# MCU.net
KiCad netlist of a schematic drawn in Altium Designer
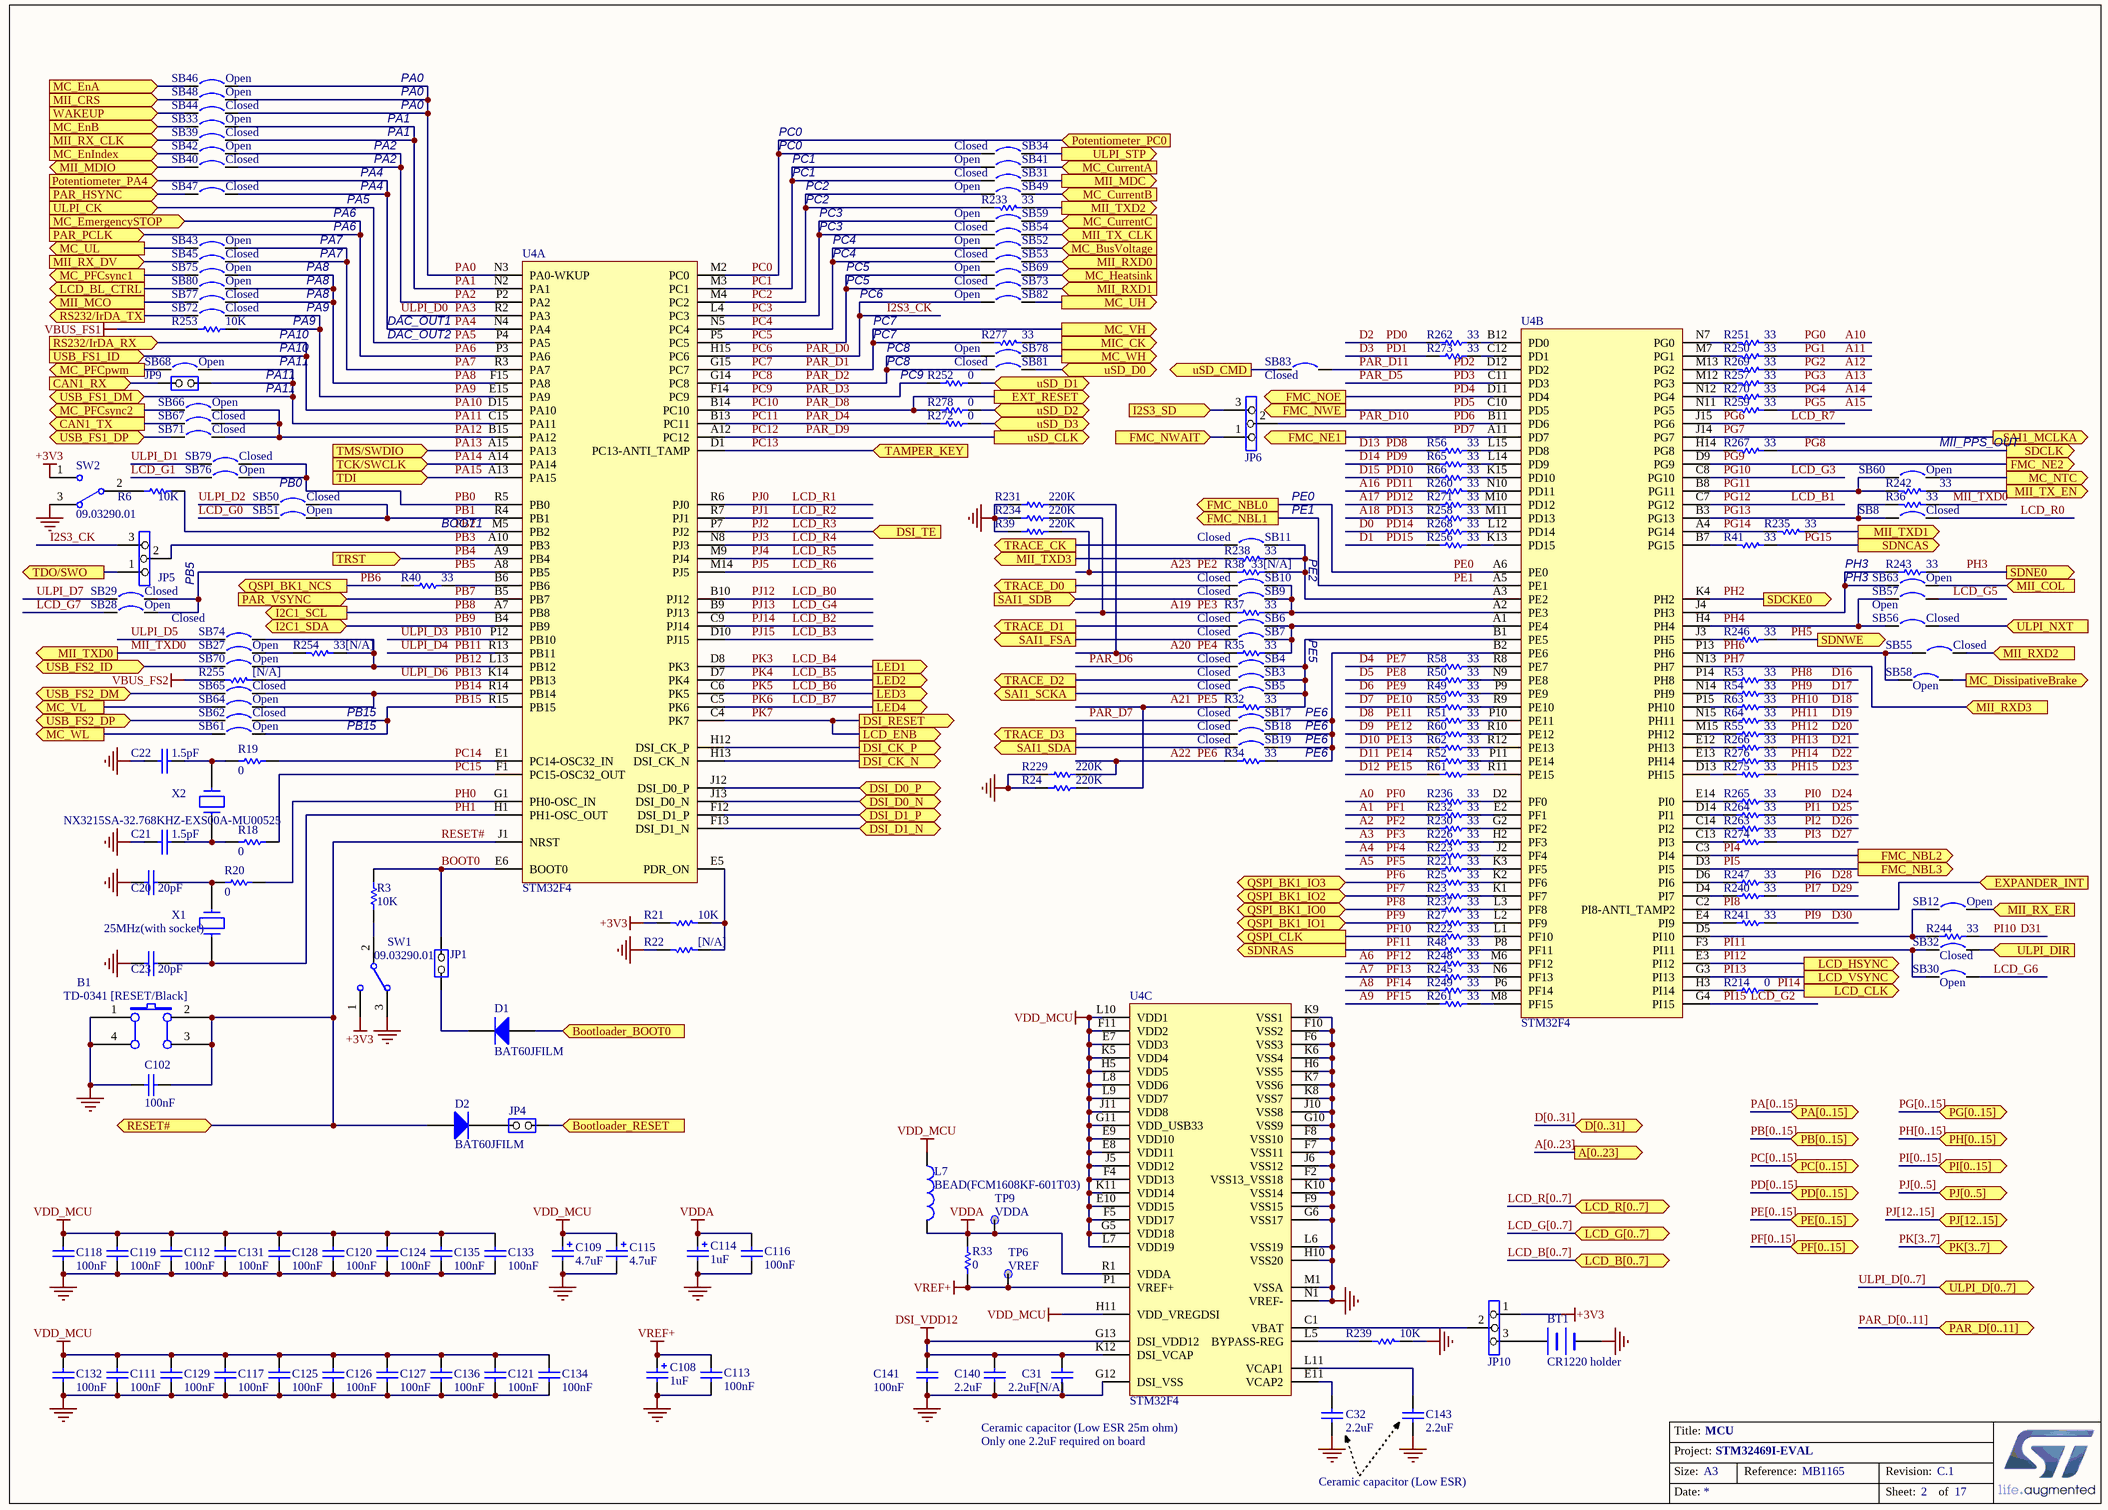
[diagram p0: MCU.SchDoc]

(export (version "E")
  (design (tool "Eeschema 10.0.6"))
  (components
    (comp (ref "B1")
      (value "TD-0341 [RESET/Black]")
      (footprint "PB10")
      (description "SE PUSHBUTTON")
      (libsource (lib "Documents") (part "SW PUSHBUTTON"))
    )
    (comp (ref "BT1")
      (value "CR1220 holder")
      (footprint "BAT_2SM_CR1220")
      (description "Battery")
      (libsource (lib "*") (part "BATTERY"))
    )
    (comp (ref "C20")
      (value "20pF")
      (footprint "0603C")
      (description "Capacitor")
      (libsource (lib "*") (part "CAP"))
    )
    (comp (ref "C21")
      (value "1.5pF")
      (footprint "0603C")
      (description "Capacitor")
      (libsource (lib "") (part "CAP_1"))
    )
    (comp (ref "C22")
      (value "1.5pF")
      (footprint "0603C")
      (description "Capacitor")
      (libsource (lib "") (part "CAP_1"))
    )
    (comp (ref "C23")
      (value "20pF")
      (footprint "0603C")
      (description "Capacitor")
      (libsource (lib "*") (part "CAP"))
    )
    (comp (ref "C31")
      (value "2.2uF[N/A]")
      (footprint "1206C")
      (description "Capacitor")
      (fields (field (name "PUBLISHER") "Altium Limited"))
      (libsource (lib "Miscellaneous Devices") (part "Cap"))
    )
    (comp (ref "C32")
      (value "2.2uF")
      (footprint "1206C")
      (description "Capacitor")
      (fields (field (name "PUBLISHER") "Altium Limited"))
      (libsource (lib "Miscellaneous Devices") (part "Cap"))
    )
    (comp (ref "C102")
      (value "100nF")
      (footprint "0603C")
      (description "Capacitor")
      (fields (field (name "PUBLISHER") "Altium Limited"))
      (libsource (lib "Miscellaneous Devices") (part "CAP"))
    )
    (comp (ref "C108")
      (value "1uF")
      (footprint "TAN-A")
      (description "Polarized Capacitor (Radial)")
      (fields (field (name "PUBLISHER") "Altium Limited"))
      (libsource (lib "Miscellaneous Devices") (part "Cap Pol1"))
    )
    (comp (ref "C109")
      (value "4.7uF")
      (footprint "TAN-A")
      (description "Polarized Capacitor (Radial)")
      (fields (field (name "PUBLISHER") "Altium Limited"))
      (libsource (lib "Miscellaneous Devices") (part "Cap Pol1"))
    )
    (comp (ref "C111")
      (value "100nF")
      (footprint "0402C")
      (description "Capacitor")
      (fields (field (name "PUBLISHER") "Altium Limited"))
      (libsource (lib "Miscellaneous Devices") (part "CAP"))
    )
    (comp (ref "C112")
      (value "100nF")
      (footprint "0402C")
      (description "Capacitor")
      (fields (field (name "PUBLISHER") "Altium Limited"))
      (libsource (lib "Miscellaneous Devices") (part "CAP"))
    )
    (comp (ref "C113")
      (value "100nF")
      (footprint "0402C")
      (description "Capacitor")
      (fields (field (name "PUBLISHER") "Altium Limited"))
      (libsource (lib "Miscellaneous Devices") (part "Cap"))
    )
    (comp (ref "C114")
      (value "1uF")
      (footprint "TAN-A")
      (description "Polarized Capacitor (Radial)")
      (fields (field (name "PUBLISHER") "Altium Limited"))
      (libsource (lib "Miscellaneous Devices") (part "Cap Pol1"))
    )
    (comp (ref "C115")
      (value "4.7uF")
      (footprint "TAN-A")
      (description "Polarized Capacitor (Radial)")
      (fields (field (name "PUBLISHER") "Altium Limited"))
      (libsource (lib "Miscellaneous Devices") (part "Cap Pol1"))
    )
    (comp (ref "C116")
      (value "100nF")
      (footprint "0402C")
      (description "Capacitor")
      (fields (field (name "PUBLISHER") "Altium Limited"))
      (libsource (lib "Miscellaneous Devices") (part "Cap"))
    )
    (comp (ref "C117")
      (value "100nF")
      (footprint "0402C")
      (description "Capacitor")
      (fields (field (name "PUBLISHER") "Altium Limited"))
      (libsource (lib "Miscellaneous Devices") (part "CAP"))
    )
    (comp (ref "C118")
      (value "100nF")
      (footprint "0402C")
      (description "Capacitor")
      (fields (field (name "PUBLISHER") "Altium Limited"))
      (libsource (lib "Miscellaneous Devices") (part "CAP"))
    )
    (comp (ref "C119")
      (value "100nF")
      (footprint "0402C")
      (description "Capacitor")
      (fields (field (name "PUBLISHER") "Altium Limited"))
      (libsource (lib "Miscellaneous Devices") (part "CAP"))
    )
    (comp (ref "C120")
      (value "100nF")
      (footprint "0402C")
      (description "Capacitor")
      (fields (field (name "PUBLISHER") "Altium Limited"))
      (libsource (lib "Miscellaneous Devices") (part "CAP"))
    )
    (comp (ref "C121")
      (value "100nF")
      (footprint "0402C")
      (description "Capacitor")
      (fields (field (name "PUBLISHER") "Altium Limited"))
      (libsource (lib "Miscellaneous Devices") (part "CAP"))
    )
    (comp (ref "C124")
      (value "100nF")
      (footprint "0402C")
      (description "Capacitor")
      (fields (field (name "PUBLISHER") "Altium Limited"))
      (libsource (lib "Miscellaneous Devices") (part "CAP"))
    )
    (comp (ref "C125")
      (value "100nF")
      (footprint "0402C")
      (description "Capacitor")
      (fields (field (name "PUBLISHER") "Altium Limited"))
      (libsource (lib "Miscellaneous Devices") (part "CAP"))
    )
    (comp (ref "C126")
      (value "100nF")
      (footprint "0402C")
      (description "Capacitor")
      (fields (field (name "PUBLISHER") "Altium Limited"))
      (libsource (lib "Miscellaneous Devices") (part "CAP"))
    )
    (comp (ref "C127")
      (value "100nF")
      (footprint "0402C")
      (description "Capacitor")
      (fields (field (name "PUBLISHER") "Altium Limited"))
      (libsource (lib "Miscellaneous Devices") (part "CAP"))
    )
    (comp (ref "C128")
      (value "100nF")
      (footprint "0402C")
      (description "Capacitor")
      (fields (field (name "PUBLISHER") "Altium Limited"))
      (libsource (lib "Miscellaneous Devices") (part "CAP"))
    )
    (comp (ref "C129")
      (value "100nF")
      (footprint "0402C")
      (description "Capacitor")
      (fields (field (name "PUBLISHER") "Altium Limited"))
      (libsource (lib "Miscellaneous Devices") (part "CAP"))
    )
    (comp (ref "C131")
      (value "100nF")
      (footprint "0402C")
      (description "Capacitor")
      (fields (field (name "PUBLISHER") "Altium Limited"))
      (libsource (lib "Miscellaneous Devices") (part "CAP"))
    )
    (comp (ref "C132")
      (value "100nF")
      (footprint "0402C")
      (description "Capacitor")
      (fields (field (name "PUBLISHER") "Altium Limited"))
      (libsource (lib "Miscellaneous Devices") (part "CAP"))
    )
    (comp (ref "C133")
      (value "100nF")
      (footprint "0402C")
      (description "Capacitor")
      (fields (field (name "PUBLISHER") "Altium Limited"))
      (libsource (lib "Miscellaneous Devices") (part "CAP"))
    )
    (comp (ref "C134")
      (value "100nF")
      (footprint "0402C")
      (description "Capacitor")
      (fields (field (name "PUBLISHER") "Altium Limited"))
      (libsource (lib "Miscellaneous Devices") (part "CAP"))
    )
    (comp (ref "C135")
      (value "100nF")
      (footprint "0402C")
      (description "Capacitor")
      (fields (field (name "PUBLISHER") "Altium Limited"))
      (libsource (lib "Miscellaneous Devices") (part "CAP"))
    )
    (comp (ref "C136")
      (value "100nF")
      (footprint "0402C")
      (description "Capacitor")
      (fields (field (name "PUBLISHER") "Altium Limited"))
      (libsource (lib "Miscellaneous Devices") (part "CAP"))
    )
    (comp (ref "C140")
      (value "2.2uF")
      (footprint "0402C")
      (description "Capacitor")
      (fields (field (name "PUBLISHER") "Altium Limited"))
      (libsource (lib "Miscellaneous Devices") (part "CAP"))
    )
    (comp (ref "C141")
      (value "100nF")
      (footprint "0402C")
      (description "Capacitor")
      (fields (field (name "PUBLISHER") "Altium Limited"))
      (libsource (lib "Miscellaneous Devices") (part "CAP"))
    )
    (comp (ref "C143")
      (value "2.2uF")
      (footprint "1206C")
      (description "Capacitor")
      (fields (field (name "PUBLISHER") "Altium Limited"))
      (libsource (lib "Miscellaneous Devices") (part "Cap"))
    )
    (comp (ref "D1")
      (value "BAT60JFILM")
      (footprint "SOD-323")
      (description "Default Diode")
      (fields (field (name "PUBLISHER") "Altium Limited"))
      (libsource (lib "Miscellaneous Devices") (part "Diode"))
    )
    (comp (ref "D2")
      (value "BAT60JFILM")
      (footprint "SOD-323")
      (description "Default Diode")
      (fields (field (name "PUBLISHER") "Altium Limited"))
      (libsource (lib "Miscellaneous Devices") (part "Diode"))
    )
    (comp (ref "JP1") (value "~") (footprint "SIP2") (libsource (lib "*") (part "JP2")))
    (comp (ref "JP4") (value "~") (footprint "SIP2") (libsource (lib "*") (part "JP2")))
    (comp (ref "JP5") (value "~") (footprint "SIP3") (libsource (lib "") (part "Jumper3_1")))
    (comp (ref "JP6") (value "~") (footprint "SIP3") (libsource (lib "") (part "Jumper3_1")))
    (comp (ref "JP9") (value "~") (footprint "SIP2") (libsource (lib "*") (part "JP2")))
    (comp (ref "JP10") (value "~") (footprint "SIP3") (libsource (lib "STR910_SCHLIB") (part "Jumper3")))
    (comp (ref "L7")
      (value "BEAD(FCM1608KF-601T03)")
      (footprint "0603L")
      (description "Inductor")
      (fields (field (name "PUBLISHER") "Altium Limited"))
      (libsource (lib "Miscellaneous Devices") (part "Inductor"))
    )
    (comp (ref "R3")
      (value "10K")
      (footprint "0603R")
      (description "Resistor")
      (fields (field (name "PUBLISHER") "Altium Limited"))
      (libsource (lib "Miscellaneous Devices") (part "res1"))
    )
    (comp (ref "R6")
      (value "10K")
      (footprint "0603R")
      (description "Resistor")
      (fields (field (name "PUBLISHER") "Altium Limited"))
      (libsource (lib "Miscellaneous Devices") (part "Res1"))
    )
    (comp (ref "R18")
      (value "0")
      (footprint "0603R")
      (description "Resistor")
      (fields (field (name "PUBLISHER") "Altium Limited"))
      (libsource (lib "") (part "Res1_1"))
    )
    (comp (ref "R19")
      (value "0")
      (footprint "0603R")
      (description "Resistor")
      (fields (field (name "PUBLISHER") "Altium Limited"))
      (libsource (lib "") (part "Res1_1"))
    )
    (comp (ref "R20")
      (value "0")
      (footprint "0603R")
      (description "Resistor")
      (fields (field (name "PUBLISHER") "Altium Limited"))
      (libsource (lib "Miscellaneous Devices") (part "Res1"))
    )
    (comp (ref "R21")
      (value "10K")
      (footprint "0603R")
      (description "Resistor")
      (fields (field (name "PUBLISHER") "Altium Limited"))
      (libsource (lib "Miscellaneous Devices") (part "Res1"))
    )
    (comp (ref "R22")
      (value "[N/A]")
      (footprint "0603R")
      (description "Resistor")
      (fields (field (name "PUBLISHER") "Altium Limited"))
      (libsource (lib "Miscellaneous Devices") (part "Res1"))
    )
    (comp (ref "R23")
      (value "33")
      (footprint "0402R")
      (description "Resistor")
      (fields (field (name "PUBLISHER") "Altium Limited"))
      (libsource (lib "Miscellaneous Devices") (part "Res1"))
    )
    (comp (ref "R24")
      (value "220K")
      (footprint "0603R")
      (description "Resistor")
      (fields (field (name "PUBLISHER") "Altium Limited"))
      (libsource (lib "Miscellaneous Devices") (part "res1"))
    )
    (comp (ref "R25")
      (value "33")
      (footprint "0402R")
      (description "Resistor")
      (fields (field (name "PUBLISHER") "Altium Limited"))
      (libsource (lib "Miscellaneous Devices") (part "Res1"))
    )
    (comp (ref "R27")
      (value "33")
      (footprint "0402R")
      (description "Resistor")
      (fields (field (name "PUBLISHER") "Altium Limited"))
      (libsource (lib "Miscellaneous Devices") (part "Res1"))
    )
    (comp (ref "R32")
      (value "33")
      (footprint "0402R")
      (description "Resistor")
      (fields (field (name "PUBLISHER") "Altium Limited"))
      (libsource (lib "Miscellaneous Devices") (part "Res1"))
    )
    (comp (ref "R33")
      (value "0")
      (footprint "0603R")
      (description "Resistor")
      (fields (field (name "PUBLISHER") "Altium Limited"))
      (libsource (lib "Miscellaneous Devices") (part "Res1"))
    )
    (comp (ref "R34")
      (value "33")
      (footprint "0402R")
      (description "Resistor")
      (fields (field (name "PUBLISHER") "Altium Limited"))
      (libsource (lib "Miscellaneous Devices") (part "Res1"))
    )
    (comp (ref "R35")
      (value "33")
      (footprint "0402R")
      (description "Resistor")
      (fields (field (name "PUBLISHER") "Altium Limited"))
      (libsource (lib "Miscellaneous Devices") (part "Res1"))
    )
    (comp (ref "R36")
      (value "33")
      (footprint "0603R")
      (description "Resistor")
      (fields (field (name "PUBLISHER") "Altium Limited"))
      (libsource (lib "Miscellaneous Devices") (part "Res1"))
    )
    (comp (ref "R37")
      (value "33")
      (footprint "0402R")
      (description "Resistor")
      (fields (field (name "PUBLISHER") "Altium Limited"))
      (libsource (lib "Miscellaneous Devices") (part "Res1"))
    )
    (comp (ref "R38")
      (value "33[N/A]")
      (footprint "0402R")
      (description "Resistor")
      (fields (field (name "PUBLISHER") "Altium Limited"))
      (libsource (lib "Miscellaneous Devices") (part "Res1"))
    )
    (comp (ref "R39")
      (value "220K")
      (footprint "0603R")
      (description "Resistor")
      (fields (field (name "PUBLISHER") "Altium Limited"))
      (libsource (lib "Miscellaneous Devices") (part "res1"))
    )
    (comp (ref "R40")
      (value "33")
      (footprint "0402R")
      (description "Resistor")
      (fields (field (name "PUBLISHER") "Altium Limited"))
      (libsource (lib "Miscellaneous Devices") (part "Res1"))
    )
    (comp (ref "R41")
      (value "33")
      (footprint "0402R")
      (description "Resistor")
      (fields (field (name "PUBLISHER") "Altium Limited"))
      (libsource (lib "Miscellaneous Devices") (part "Res1"))
    )
    (comp (ref "R48")
      (value "33")
      (footprint "0402R")
      (description "Resistor")
      (fields (field (name "PUBLISHER") "Altium Limited"))
      (libsource (lib "Miscellaneous Devices") (part "Res1"))
    )
    (comp (ref "R49")
      (value "33")
      (footprint "0402R")
      (description "Resistor")
      (fields (field (name "PUBLISHER") "Altium Limited"))
      (libsource (lib "Miscellaneous Devices") (part "Res1"))
    )
    (comp (ref "R50")
      (value "33")
      (footprint "0402R")
      (description "Resistor")
      (fields (field (name "PUBLISHER") "Altium Limited"))
      (libsource (lib "Miscellaneous Devices") (part "Res1"))
    )
    (comp (ref "R51")
      (value "33")
      (footprint "0402R")
      (description "Resistor")
      (fields (field (name "PUBLISHER") "Altium Limited"))
      (libsource (lib "Miscellaneous Devices") (part "Res1"))
    )
    (comp (ref "R52")
      (value "33")
      (footprint "0402R")
      (description "Resistor")
      (fields (field (name "PUBLISHER") "Altium Limited"))
      (libsource (lib "Miscellaneous Devices") (part "Res1"))
    )
    (comp (ref "R53")
      (value "33")
      (footprint "0402R")
      (description "Resistor")
      (fields (field (name "PUBLISHER") "Altium Limited"))
      (libsource (lib "Miscellaneous Devices") (part "Res1"))
    )
    (comp (ref "R54")
      (value "33")
      (footprint "0402R")
      (description "Resistor")
      (fields (field (name "PUBLISHER") "Altium Limited"))
      (libsource (lib "Miscellaneous Devices") (part "Res1"))
    )
    (comp (ref "R55")
      (value "33")
      (footprint "0402R")
      (description "Resistor")
      (fields (field (name "PUBLISHER") "Altium Limited"))
      (libsource (lib "Miscellaneous Devices") (part "Res1"))
    )
    (comp (ref "R56")
      (value "33")
      (footprint "0402R")
      (description "Resistor")
      (fields (field (name "PUBLISHER") "Altium Limited"))
      (libsource (lib "Miscellaneous Devices") (part "Res1"))
    )
    (comp (ref "R58")
      (value "33")
      (footprint "0402R")
      (description "Resistor")
      (fields (field (name "PUBLISHER") "Altium Limited"))
      (libsource (lib "Miscellaneous Devices") (part "Res1"))
    )
    (comp (ref "R59")
      (value "33")
      (footprint "0402R")
      (description "Resistor")
      (fields (field (name "PUBLISHER") "Altium Limited"))
      (libsource (lib "Miscellaneous Devices") (part "Res1"))
    )
    (comp (ref "R60")
      (value "33")
      (footprint "0402R")
      (description "Resistor")
      (fields (field (name "PUBLISHER") "Altium Limited"))
      (libsource (lib "Miscellaneous Devices") (part "Res1"))
    )
    (comp (ref "R61")
      (value "33")
      (footprint "0402R")
      (description "Resistor")
      (fields (field (name "PUBLISHER") "Altium Limited"))
      (libsource (lib "Miscellaneous Devices") (part "Res1"))
    )
    (comp (ref "R62")
      (value "33")
      (footprint "0402R")
      (description "Resistor")
      (fields (field (name "PUBLISHER") "Altium Limited"))
      (libsource (lib "Miscellaneous Devices") (part "Res1"))
    )
    (comp (ref "R63")
      (value "33")
      (footprint "0402R")
      (description "Resistor")
      (fields (field (name "PUBLISHER") "Altium Limited"))
      (libsource (lib "Miscellaneous Devices") (part "Res1"))
    )
    (comp (ref "R64")
      (value "33")
      (footprint "0402R")
      (description "Resistor")
      (fields (field (name "PUBLISHER") "Altium Limited"))
      (libsource (lib "Miscellaneous Devices") (part "Res1"))
    )
    (comp (ref "R65")
      (value "33")
      (footprint "0402R")
      (description "Resistor")
      (fields (field (name "PUBLISHER") "Altium Limited"))
      (libsource (lib "Miscellaneous Devices") (part "Res1"))
    )
    (comp (ref "R66")
      (value "33")
      (footprint "0402R")
      (description "Resistor")
      (fields (field (name "PUBLISHER") "Altium Limited"))
      (libsource (lib "Miscellaneous Devices") (part "Res1"))
    )
    (comp (ref "R214")
      (value "0")
      (footprint "0603R")
      (description "Resistor")
      (fields (field (name "PUBLISHER") "Altium Limited"))
      (libsource (lib "Miscellaneous Devices") (part "Res1"))
    )
    (comp (ref "R221")
      (value "33")
      (footprint "0402R")
      (description "Resistor")
      (fields (field (name "PUBLISHER") "Altium Limited"))
      (libsource (lib "Miscellaneous Devices") (part "Res1"))
    )
    (comp (ref "R222")
      (value "33")
      (footprint "0402R")
      (description "Resistor")
      (fields (field (name "PUBLISHER") "Altium Limited"))
      (libsource (lib "Miscellaneous Devices") (part "Res1"))
    )
    (comp (ref "R223")
      (value "33")
      (footprint "0402R")
      (description "Resistor")
      (fields (field (name "PUBLISHER") "Altium Limited"))
      (libsource (lib "Miscellaneous Devices") (part "Res1"))
    )
    (comp (ref "R226")
      (value "33")
      (footprint "0402R")
      (description "Resistor")
      (fields (field (name "PUBLISHER") "Altium Limited"))
      (libsource (lib "Miscellaneous Devices") (part "Res1"))
    )
    (comp (ref "R229")
      (value "220K")
      (footprint "0603R")
      (description "Resistor")
      (fields (field (name "PUBLISHER") "Altium Limited"))
      (libsource (lib "Miscellaneous Devices") (part "res1"))
    )
    (comp (ref "R230")
      (value "33")
      (footprint "0402R")
      (description "Resistor")
      (fields (field (name "PUBLISHER") "Altium Limited"))
      (libsource (lib "Miscellaneous Devices") (part "Res1"))
    )
    (comp (ref "R231")
      (value "220K")
      (footprint "0603R")
      (description "Resistor")
      (fields (field (name "PUBLISHER") "Altium Limited"))
      (libsource (lib "Miscellaneous Devices") (part "res1"))
    )
    (comp (ref "R232")
      (value "33")
      (footprint "0402R")
      (description "Resistor")
      (fields (field (name "PUBLISHER") "Altium Limited"))
      (libsource (lib "Miscellaneous Devices") (part "Res1"))
    )
    (comp (ref "R233")
      (value "33")
      (footprint "0603R")
      (description "Resistor")
      (fields (field (name "PUBLISHER") "Altium Limited"))
      (libsource (lib "Miscellaneous Devices") (part "Res1"))
    )
    (comp (ref "R234")
      (value "220K")
      (footprint "0603R")
      (description "Resistor")
      (fields (field (name "PUBLISHER") "Altium Limited"))
      (libsource (lib "Miscellaneous Devices") (part "res1"))
    )
    (comp (ref "R235")
      (value "33")
      (footprint "0603R")
      (description "Resistor")
      (fields (field (name "PUBLISHER") "Altium Limited"))
      (libsource (lib "Miscellaneous Devices") (part "Res1"))
    )
    (comp (ref "R236")
      (value "33")
      (footprint "0402R")
      (description "Resistor")
      (fields (field (name "PUBLISHER") "Altium Limited"))
      (libsource (lib "Miscellaneous Devices") (part "Res1"))
    )
    (comp (ref "R237")
      (value "33")
      (footprint "0402R")
      (description "Resistor")
      (fields (field (name "PUBLISHER") "Altium Limited"))
      (libsource (lib "Miscellaneous Devices") (part "Res1"))
    )
    (comp (ref "R238")
      (value "33")
      (footprint "0603R")
      (description "Resistor")
      (fields (field (name "PUBLISHER") "Altium Limited"))
      (libsource (lib "Miscellaneous Devices") (part "Res1"))
    )
    (comp (ref "R239")
      (value "10K")
      (footprint "0603R")
      (description "Resistor")
      (fields (field (name "PUBLISHER") "Altium Limited"))
      (libsource (lib "") (part "Res1_1"))
    )
    (comp (ref "R240")
      (value "33")
      (footprint "0402R")
      (description "Resistor")
      (fields (field (name "PUBLISHER") "Altium Limited"))
      (libsource (lib "Miscellaneous Devices") (part "Res1"))
    )
    (comp (ref "R241")
      (value "33")
      (footprint "0402R")
      (description "Resistor")
      (fields (field (name "PUBLISHER") "Altium Limited"))
      (libsource (lib "Miscellaneous Devices") (part "Res1"))
    )
    (comp (ref "R242")
      (value "33")
      (footprint "0603R")
      (description "Resistor")
      (fields (field (name "PUBLISHER") "Altium Limited"))
      (libsource (lib "Miscellaneous Devices") (part "Res1"))
    )
    (comp (ref "R243")
      (value "33")
      (footprint "0402R")
      (description "Resistor")
      (fields (field (name "PUBLISHER") "Altium Limited"))
      (libsource (lib "Miscellaneous Devices") (part "Res1"))
    )
    (comp (ref "R244")
      (value "33")
      (footprint "0402R")
      (description "Resistor")
      (fields (field (name "PUBLISHER") "Altium Limited"))
      (libsource (lib "Miscellaneous Devices") (part "Res1"))
    )
    (comp (ref "R245")
      (value "33")
      (footprint "0402R")
      (description "Resistor")
      (fields (field (name "PUBLISHER") "Altium Limited"))
      (libsource (lib "Miscellaneous Devices") (part "Res1"))
    )
    (comp (ref "R246")
      (value "33")
      (footprint "0402R")
      (description "Resistor")
      (fields (field (name "PUBLISHER") "Altium Limited"))
      (libsource (lib "Miscellaneous Devices") (part "Res1"))
    )
    (comp (ref "R247")
      (value "33")
      (footprint "0402R")
      (description "Resistor")
      (fields (field (name "PUBLISHER") "Altium Limited"))
      (libsource (lib "Miscellaneous Devices") (part "Res1"))
    )
    (comp (ref "R248")
      (value "33")
      (footprint "0402R")
      (description "Resistor")
      (fields (field (name "PUBLISHER") "Altium Limited"))
      (libsource (lib "Miscellaneous Devices") (part "Res1"))
    )
    (comp (ref "R249")
      (value "33")
      (footprint "0402R")
      (description "Resistor")
      (fields (field (name "PUBLISHER") "Altium Limited"))
      (libsource (lib "Miscellaneous Devices") (part "Res1"))
    )
    (comp (ref "R250")
      (value "33")
      (footprint "0402R")
      (description "Resistor")
      (fields (field (name "PUBLISHER") "Altium Limited"))
      (libsource (lib "Miscellaneous Devices") (part "Res1"))
    )
    (comp (ref "R251")
      (value "33")
      (footprint "0402R")
      (description "Resistor")
      (fields (field (name "PUBLISHER") "Altium Limited"))
      (libsource (lib "Miscellaneous Devices") (part "Res1"))
    )
    (comp (ref "R252")
      (value "0")
      (footprint "0603R")
      (description "Resistor")
      (fields (field (name "PUBLISHER") "Altium Limited"))
      (libsource (lib "Miscellaneous Devices") (part "Res1"))
    )
    (comp (ref "R253")
      (value "10K")
      (footprint "0603R")
      (description "Resistor")
      (fields (field (name "PUBLISHER") "Altium Limited"))
      (libsource (lib "Miscellaneous Devices") (part "res1"))
    )
    (comp (ref "R254")
      (value "33[N/A]")
      (footprint "0603R")
      (description "Resistor")
      (fields (field (name "PUBLISHER") "Altium Limited"))
      (libsource (lib "Miscellaneous Devices") (part "Res1"))
    )
    (comp (ref "R255")
      (value "[N/A]")
      (footprint "0603R")
      (description "Resistor")
      (fields (field (name "PUBLISHER") "Altium Limited"))
      (libsource (lib "Miscellaneous Devices") (part "Res1"))
    )
    (comp (ref "R256")
      (value "33")
      (footprint "0402R")
      (description "Resistor")
      (fields (field (name "PUBLISHER") "Altium Limited"))
      (libsource (lib "Miscellaneous Devices") (part "Res1"))
    )
    (comp (ref "R257")
      (value "33")
      (footprint "0402R")
      (description "Resistor")
      (fields (field (name "PUBLISHER") "Altium Limited"))
      (libsource (lib "Miscellaneous Devices") (part "Res1"))
    )
    (comp (ref "R258")
      (value "33")
      (footprint "0402R")
      (description "Resistor")
      (fields (field (name "PUBLISHER") "Altium Limited"))
      (libsource (lib "Miscellaneous Devices") (part "Res1"))
    )
    (comp (ref "R259")
      (value "33")
      (footprint "0402R")
      (description "Resistor")
      (fields (field (name "PUBLISHER") "Altium Limited"))
      (libsource (lib "Miscellaneous Devices") (part "Res1"))
    )
    (comp (ref "R260")
      (value "33")
      (footprint "0402R")
      (description "Resistor")
      (fields (field (name "PUBLISHER") "Altium Limited"))
      (libsource (lib "Miscellaneous Devices") (part "Res1"))
    )
    (comp (ref "R261")
      (value "33")
      (footprint "0402R")
      (description "Resistor")
      (fields (field (name "PUBLISHER") "Altium Limited"))
      (libsource (lib "Miscellaneous Devices") (part "Res1"))
    )
    (comp (ref "R262")
      (value "33")
      (footprint "0402R")
      (description "Resistor")
      (fields (field (name "PUBLISHER") "Altium Limited"))
      (libsource (lib "Miscellaneous Devices") (part "Res1"))
    )
    (comp (ref "R263")
      (value "33")
      (footprint "0402R")
      (description "Resistor")
      (fields (field (name "PUBLISHER") "Altium Limited"))
      (libsource (lib "Miscellaneous Devices") (part "Res1"))
    )
    (comp (ref "R264")
      (value "33")
      (footprint "0402R")
      (description "Resistor")
      (fields (field (name "PUBLISHER") "Altium Limited"))
      (libsource (lib "Miscellaneous Devices") (part "Res1"))
    )
    (comp (ref "R265")
      (value "33")
      (footprint "0402R")
      (description "Resistor")
      (fields (field (name "PUBLISHER") "Altium Limited"))
      (libsource (lib "Miscellaneous Devices") (part "Res1"))
    )
    (comp (ref "R266")
      (value "33")
      (footprint "0402R")
      (description "Resistor")
      (fields (field (name "PUBLISHER") "Altium Limited"))
      (libsource (lib "Miscellaneous Devices") (part "Res1"))
    )
    (comp (ref "R267")
      (value "33")
      (footprint "0402R")
      (description "Resistor")
      (fields (field (name "PUBLISHER") "Altium Limited"))
      (libsource (lib "Miscellaneous Devices") (part "Res1"))
    )
    (comp (ref "R268")
      (value "33")
      (footprint "0402R")
      (description "Resistor")
      (fields (field (name "PUBLISHER") "Altium Limited"))
      (libsource (lib "Miscellaneous Devices") (part "Res1"))
    )
    (comp (ref "R269")
      (value "33")
      (footprint "0402R")
      (description "Resistor")
      (fields (field (name "PUBLISHER") "Altium Limited"))
      (libsource (lib "Miscellaneous Devices") (part "Res1"))
    )
    (comp (ref "R270")
      (value "33")
      (footprint "0402R")
      (description "Resistor")
      (fields (field (name "PUBLISHER") "Altium Limited"))
      (libsource (lib "Miscellaneous Devices") (part "Res1"))
    )
    (comp (ref "R271")
      (value "33")
      (footprint "0402R")
      (description "Resistor")
      (fields (field (name "PUBLISHER") "Altium Limited"))
      (libsource (lib "Miscellaneous Devices") (part "Res1"))
    )
    (comp (ref "R272")
      (value "0")
      (footprint "0603R")
      (description "Resistor")
      (fields (field (name "PUBLISHER") "Altium Limited"))
      (libsource (lib "Miscellaneous Devices") (part "Res1"))
    )
    (comp (ref "R273")
      (value "33")
      (footprint "0402R")
      (description "Resistor")
      (fields (field (name "PUBLISHER") "Altium Limited"))
      (libsource (lib "Miscellaneous Devices") (part "Res1"))
    )
    (comp (ref "R274")
      (value "33")
      (footprint "0402R")
      (description "Resistor")
      (fields (field (name "PUBLISHER") "Altium Limited"))
      (libsource (lib "Miscellaneous Devices") (part "Res1"))
    )
    (comp (ref "R275")
      (value "33")
      (footprint "0402R")
      (description "Resistor")
      (fields (field (name "PUBLISHER") "Altium Limited"))
      (libsource (lib "Miscellaneous Devices") (part "Res1"))
    )
    (comp (ref "R276")
      (value "33")
      (footprint "0402R")
      (description "Resistor")
      (fields (field (name "PUBLISHER") "Altium Limited"))
      (libsource (lib "Miscellaneous Devices") (part "Res1"))
    )
    (comp (ref "R277")
      (value "33")
      (footprint "0603R")
      (description "Resistor")
      (fields (field (name "PUBLISHER") "Altium Limited"))
      (libsource (lib "Miscellaneous Devices") (part "Res1"))
    )
    (comp (ref "R278")
      (value "0")
      (footprint "0603R")
      (description "Resistor")
      (fields (field (name "PUBLISHER") "Altium Limited"))
      (libsource (lib "Miscellaneous Devices") (part "Res1"))
    )
    (comp (ref "SB3")
      (value "Closed")
      (footprint "SB_0603")
      (description "Circuit Breaker")
      (fields (field (name "PUBLISHER") "Altium Limited"))
      (libsource (lib "MB1165") (part "Circuit Breaker_close"))
    )
    (comp (ref "SB4")
      (value "Closed")
      (footprint "SB_0603")
      (description "Circuit Breaker")
      (fields (field (name "PUBLISHER") "Altium Limited"))
      (libsource (lib "MB1165") (part "Circuit Breaker_close"))
    )
    (comp (ref "SB5")
      (value "Closed")
      (footprint "SB_0603")
      (description "Circuit Breaker")
      (fields (field (name "PUBLISHER") "Altium Limited"))
      (libsource (lib "MB1165") (part "Circuit Breaker_close"))
    )
    (comp (ref "SB6")
      (value "Closed")
      (footprint "SB_0603")
      (description "Circuit Breaker")
      (fields (field (name "PUBLISHER") "Altium Limited"))
      (libsource (lib "MB1165") (part "Circuit Breaker_close"))
    )
    (comp (ref "SB7")
      (value "Closed")
      (footprint "SB_0603")
      (description "Circuit Breaker")
      (fields (field (name "PUBLISHER") "Altium Limited"))
      (libsource (lib "MB1165") (part "Circuit Breaker_close"))
    )
    (comp (ref "SB8")
      (value "Closed")
      (footprint "SB_0603")
      (description "Circuit Breaker")
      (fields (field (name "PUBLISHER") "Altium Limited"))
      (libsource (lib "MB1165") (part "Circuit Breaker_close"))
    )
    (comp (ref "SB9")
      (value "Closed")
      (footprint "SB_0603")
      (description "Circuit Breaker")
      (fields (field (name "PUBLISHER") "Altium Limited"))
      (libsource (lib "MB1165") (part "Circuit Breaker_close"))
    )
    (comp (ref "SB10")
      (value "Closed")
      (footprint "SB_0603")
      (description "Circuit Breaker")
      (fields (field (name "PUBLISHER") "Altium Limited"))
      (libsource (lib "MB1165") (part "Circuit Breaker_close"))
    )
    (comp (ref "SB11")
      (value "Closed")
      (footprint "SB_0603")
      (description "Circuit Breaker")
      (fields (field (name "PUBLISHER") "Altium Limited"))
      (libsource (lib "MB1165") (part "Circuit Breaker_close"))
    )
    (comp (ref "SB12")
      (value "Open")
      (footprint "SB_0603")
      (description "Circuit Breaker")
      (fields (field (name "PUBLISHER") "Altium Limited"))
      (libsource (lib "MB1165") (part "Circuit Breaker"))
    )
    (comp (ref "SB17")
      (value "Closed")
      (footprint "SB_0603")
      (description "Circuit Breaker")
      (fields (field (name "PUBLISHER") "Altium Limited"))
      (libsource (lib "MB1165") (part "Circuit Breaker_close"))
    )
    (comp (ref "SB18")
      (value "Closed")
      (footprint "SB_0603")
      (description "Circuit Breaker")
      (fields (field (name "PUBLISHER") "Altium Limited"))
      (libsource (lib "MB1165") (part "Circuit Breaker_close"))
    )
    (comp (ref "SB19")
      (value "Closed")
      (footprint "SB_0603")
      (description "Circuit Breaker")
      (fields (field (name "PUBLISHER") "Altium Limited"))
      (libsource (lib "MB1165") (part "Circuit Breaker_close"))
    )
    (comp (ref "SB27")
      (value "Open")
      (footprint "SB_0603")
      (description "Circuit Breaker")
      (fields (field (name "PUBLISHER") "Altium Limited"))
      (libsource (lib "MB1165") (part "Circuit Breaker"))
    )
    (comp (ref "SB28")
      (value "Open")
      (footprint "SB_0603")
      (description "Circuit Breaker")
      (fields (field (name "PUBLISHER") "Altium Limited"))
      (libsource (lib "MB1165") (part "Circuit Breaker"))
    )
    (comp (ref "SB29")
      (value "Closed")
      (footprint "SB_0603")
      (description "Circuit Breaker")
      (fields (field (name "PUBLISHER") "Altium Limited"))
      (libsource (lib "MB1165") (part "Circuit Breaker_close"))
    )
    (comp (ref "SB30")
      (value "Open")
      (footprint "SB_0603")
      (description "Circuit Breaker")
      (fields (field (name "PUBLISHER") "Altium Limited"))
      (libsource (lib "MB1165") (part "Circuit Breaker"))
    )
    (comp (ref "SB31")
      (value "Closed")
      (footprint "SB_0603")
      (description "Circuit Breaker")
      (fields (field (name "PUBLISHER") "Altium Limited"))
      (libsource (lib "MB1165") (part "Circuit Breaker_close"))
    )
    (comp (ref "SB32")
      (value "Closed")
      (footprint "SB_0603")
      (description "Circuit Breaker")
      (fields (field (name "PUBLISHER") "Altium Limited"))
      (libsource (lib "MB1165") (part "Circuit Breaker_close"))
    )
    (comp (ref "SB33")
      (value "Open")
      (footprint "SB_0603")
      (description "Circuit Breaker")
      (fields (field (name "PUBLISHER") "Altium Limited"))
      (libsource (lib "MB1165") (part "Circuit Breaker"))
    )
    (comp (ref "SB34")
      (value "Closed")
      (footprint "SB_0603")
      (description "Circuit Breaker")
      (fields (field (name "PUBLISHER") "Altium Limited"))
      (libsource (lib "MB1165") (part "Circuit Breaker_close"))
    )
    (comp (ref "SB39")
      (value "Closed")
      (footprint "SB_0603")
      (description "Circuit Breaker")
      (fields (field (name "PUBLISHER") "Altium Limited"))
      (libsource (lib "MB1165") (part "Circuit Breaker_close"))
    )
    (comp (ref "SB40")
      (value "Closed")
      (footprint "SB_0603")
      (description "Circuit Breaker")
      (fields (field (name "PUBLISHER") "Altium Limited"))
      (libsource (lib "MB1165") (part "Circuit Breaker_close"))
    )
    (comp (ref "SB41")
      (value "Open")
      (footprint "SB_0603")
      (description "Circuit Breaker")
      (fields (field (name "PUBLISHER") "Altium Limited"))
      (libsource (lib "MB1165") (part "Circuit Breaker"))
    )
    (comp (ref "SB42")
      (value "Open")
      (footprint "SB_0603")
      (description "Circuit Breaker")
      (fields (field (name "PUBLISHER") "Altium Limited"))
      (libsource (lib "MB1165") (part "Circuit Breaker"))
    )
    (comp (ref "SB43")
      (value "Open")
      (footprint "SB_0603")
      (description "Circuit Breaker")
      (fields (field (name "PUBLISHER") "Altium Limited"))
      (libsource (lib "MB1165") (part "Circuit Breaker"))
    )
    (comp (ref "SB44")
      (value "Closed")
      (footprint "SB_0603")
      (description "Circuit Breaker")
      (fields (field (name "PUBLISHER") "Altium Limited"))
      (libsource (lib "MB1165") (part "Circuit Breaker_close"))
    )
    (comp (ref "SB45")
      (value "Closed")
      (footprint "SB_0603")
      (description "Circuit Breaker")
      (fields (field (name "PUBLISHER") "Altium Limited"))
      (libsource (lib "MB1165") (part "Circuit Breaker_close"))
    )
    (comp (ref "SB46")
      (value "Open")
      (footprint "SB_0603")
      (description "Circuit Breaker")
      (fields (field (name "PUBLISHER") "Altium Limited"))
      (libsource (lib "MB1165") (part "Circuit Breaker"))
    )
    (comp (ref "SB47")
      (value "Closed")
      (footprint "SB_0603")
      (description "Circuit Breaker")
      (fields (field (name "PUBLISHER") "Altium Limited"))
      (libsource (lib "MB1165") (part "Circuit Breaker_close"))
    )
    (comp (ref "SB48")
      (value "Open")
      (footprint "SB_0603")
      (description "Circuit Breaker")
      (fields (field (name "PUBLISHER") "Altium Limited"))
      (libsource (lib "MB1165") (part "Circuit Breaker"))
    )
    (comp (ref "SB49")
      (value "Open")
      (footprint "SB_0603")
      (description "Circuit Breaker")
      (fields (field (name "PUBLISHER") "Altium Limited"))
      (libsource (lib "MB1165") (part "Circuit Breaker"))
    )
    (comp (ref "SB50")
      (value "Closed")
      (footprint "SB_0603")
      (description "Circuit Breaker")
      (fields (field (name "PUBLISHER") "Altium Limited"))
      (libsource (lib "MB1165") (part "Circuit Breaker_close"))
    )
    (comp (ref "SB51")
      (value "Open")
      (footprint "SB_0603")
      (description "Circuit Breaker")
      (fields (field (name "PUBLISHER") "Altium Limited"))
      (libsource (lib "MB1165") (part "Circuit Breaker"))
    )
    (comp (ref "SB52")
      (value "Open")
      (footprint "SB_0603")
      (description "Circuit Breaker")
      (fields (field (name "PUBLISHER") "Altium Limited"))
      (libsource (lib "MB1165") (part "Circuit Breaker"))
    )
    (comp (ref "SB53")
      (value "Closed")
      (footprint "SB_0603")
      (description "Circuit Breaker")
      (fields (field (name "PUBLISHER") "Altium Limited"))
      (libsource (lib "MB1165") (part "Circuit Breaker_close"))
    )
    (comp (ref "SB54")
      (value "Closed")
      (footprint "SB_0603")
      (description "Circuit Breaker")
      (fields (field (name "PUBLISHER") "Altium Limited"))
      (libsource (lib "MB1165") (part "Circuit Breaker_close"))
    )
    (comp (ref "SB55")
      (value "Closed")
      (footprint "SB_0603")
      (description "Circuit Breaker")
      (fields (field (name "PUBLISHER") "Altium Limited"))
      (libsource (lib "MB1165") (part "Circuit Breaker_close"))
    )
    (comp (ref "SB56")
      (value "Closed")
      (footprint "SB_0603")
      (description "Circuit Breaker")
      (fields (field (name "PUBLISHER") "Altium Limited"))
      (libsource (lib "MB1165") (part "Circuit Breaker_close"))
    )
    (comp (ref "SB57")
      (value "Open")
      (footprint "SB_0603")
      (description "Circuit Breaker")
      (fields (field (name "PUBLISHER") "Altium Limited"))
      (libsource (lib "MB1165") (part "Circuit Breaker"))
    )
    (comp (ref "SB58")
      (value "Open")
      (footprint "SB_0603")
      (description "Circuit Breaker")
      (fields (field (name "PUBLISHER") "Altium Limited"))
      (libsource (lib "MB1165") (part "Circuit Breaker"))
    )
    (comp (ref "SB59")
      (value "Open")
      (footprint "SB_0603")
      (description "Circuit Breaker")
      (fields (field (name "PUBLISHER") "Altium Limited"))
      (libsource (lib "MB1165") (part "Circuit Breaker"))
    )
    (comp (ref "SB60")
      (value "Open")
      (footprint "SB_0603")
      (description "Circuit Breaker")
      (fields (field (name "PUBLISHER") "Altium Limited"))
      (libsource (lib "MB1165") (part "Circuit Breaker"))
    )
    (comp (ref "SB61")
      (value "Open")
      (footprint "SB_0603")
      (description "Circuit Breaker")
      (fields (field (name "PUBLISHER") "Altium Limited"))
      (libsource (lib "MB1165") (part "Circuit Breaker"))
    )
    (comp (ref "SB62")
      (value "Closed")
      (footprint "SB_0603")
      (description "Circuit Breaker")
      (fields (field (name "PUBLISHER") "Altium Limited"))
      (libsource (lib "MB1165") (part "Circuit Breaker_close"))
    )
    (comp (ref "SB63")
      (value "Open")
      (footprint "SB_0603")
      (description "Circuit Breaker")
      (fields (field (name "PUBLISHER") "Altium Limited"))
      (libsource (lib "MB1165") (part "Circuit Breaker"))
    )
    (comp (ref "SB64")
      (value "Open")
      (footprint "SB_0603")
      (description "Circuit Breaker")
      (fields (field (name "PUBLISHER") "Altium Limited"))
      (libsource (lib "MB1165") (part "Circuit Breaker"))
    )
    (comp (ref "SB65")
      (value "Closed")
      (footprint "SB_0603")
      (description "Circuit Breaker")
      (fields (field (name "PUBLISHER") "Altium Limited"))
      (libsource (lib "MB1165") (part "Circuit Breaker_close"))
    )
    (comp (ref "SB66")
      (value "Open")
      (footprint "SB_0603")
      (description "Circuit Breaker")
      (fields (field (name "PUBLISHER") "Altium Limited"))
      (libsource (lib "MB1165") (part "Circuit Breaker"))
    )
    (comp (ref "SB67")
      (value "Closed")
      (footprint "SB_0603")
      (description "Circuit Breaker")
      (fields (field (name "PUBLISHER") "Altium Limited"))
      (libsource (lib "MB1165") (part "Circuit Breaker_close"))
    )
    (comp (ref "SB68")
      (value "Open")
      (footprint "SB_0603")
      (description "Circuit Breaker")
      (fields (field (name "PUBLISHER") "Altium Limited"))
      (libsource (lib "MB1165") (part "Circuit Breaker"))
    )
    (comp (ref "SB69")
      (value "Open")
      (footprint "SB_0603")
      (description "Circuit Breaker")
      (fields (field (name "PUBLISHER") "Altium Limited"))
      (libsource (lib "MB1165") (part "Circuit Breaker"))
    )
    (comp (ref "SB70")
      (value "Open")
      (footprint "SB_0603")
      (description "Circuit Breaker")
      (fields (field (name "PUBLISHER") "Altium Limited"))
      (libsource (lib "MB1165") (part "Circuit Breaker"))
    )
    (comp (ref "SB71")
      (value "Closed")
      (footprint "SB_0603")
      (description "Circuit Breaker")
      (fields (field (name "PUBLISHER") "Altium Limited"))
      (libsource (lib "MB1165") (part "Circuit Breaker_close"))
    )
    (comp (ref "SB72")
      (value "Closed")
      (footprint "SB_0603")
      (description "Circuit Breaker")
      (fields (field (name "PUBLISHER") "Altium Limited"))
      (libsource (lib "MB1165") (part "Circuit Breaker_close"))
    )
    (comp (ref "SB73")
      (value "Closed")
      (footprint "SB_0603")
      (description "Circuit Breaker")
      (fields (field (name "PUBLISHER") "Altium Limited"))
      (libsource (lib "MB1165") (part "Circuit Breaker_close"))
    )
    (comp (ref "SB74")
      (value "Closed")
      (footprint "SB_0603")
      (description "Circuit Breaker")
      (fields (field (name "PUBLISHER") "Altium Limited"))
      (libsource (lib "MB1165") (part "Circuit Breaker_close"))
    )
    (comp (ref "SB75")
      (value "Open")
      (footprint "SB_0603")
      (description "Circuit Breaker")
      (fields (field (name "PUBLISHER") "Altium Limited"))
      (libsource (lib "MB1165") (part "Circuit Breaker"))
    )
    (comp (ref "SB76")
      (value "Open")
      (footprint "SB_0603")
      (description "Circuit Breaker")
      (fields (field (name "PUBLISHER") "Altium Limited"))
      (libsource (lib "MB1165") (part "Circuit Breaker"))
    )
    (comp (ref "SB77")
      (value "Closed")
      (footprint "SB_0603")
      (description "Circuit Breaker")
      (fields (field (name "PUBLISHER") "Altium Limited"))
      (libsource (lib "MB1165") (part "Circuit Breaker_close"))
    )
    (comp (ref "SB78")
      (value "Open")
      (footprint "SB_0603")
      (description "Circuit Breaker")
      (fields (field (name "PUBLISHER") "Altium Limited"))
      (libsource (lib "MB1165") (part "Circuit Breaker"))
    )
    (comp (ref "SB79")
      (value "Closed")
      (footprint "SB_0603")
      (description "Circuit Breaker")
      (fields (field (name "PUBLISHER") "Altium Limited"))
      (libsource (lib "MB1165") (part "Circuit Breaker_close"))
    )
    (comp (ref "SB80")
      (value "Open")
      (footprint "SB_0603")
      (description "Circuit Breaker")
      (fields (field (name "PUBLISHER") "Altium Limited"))
      (libsource (lib "MB1165") (part "Circuit Breaker"))
    )
    (comp (ref "SB81")
      (value "Closed")
      (footprint "SB_0603")
      (description "Circuit Breaker")
      (fields (field (name "PUBLISHER") "Altium Limited"))
      (libsource (lib "MB1165") (part "Circuit Breaker_close"))
    )
    (comp (ref "SB82")
      (value "Open")
      (footprint "SB_0603")
      (description "Circuit Breaker")
      (fields (field (name "PUBLISHER") "Altium Limited"))
      (libsource (lib "MB1165") (part "Circuit Breaker"))
    )
    (comp (ref "SB83")
      (value "Closed")
      (footprint "SB_0603")
      (description "Circuit Breaker")
      (fields (field (name "PUBLISHER") "Altium Limited"))
      (libsource (lib "MB1165") (part "Circuit Breaker_close"))
    )
    (comp (ref "SW1")
      (value "09.03290.01")
      (footprint "SW1_3TH_2R54_10X2R5")
      (description "SPDT Subminiature Toggle Switch, Right Angle Mounting, Vertical Actuation")
      (fields (field (name "PUBLISHER") "Altium Limited"))
      (libsource (lib "mb1045") (part "SW-SPDT"))
    )
    (comp (ref "SW2")
      (value "09.03290.01")
      (footprint "SW1_3TH_2R54_10X2R5")
      (description "SPDT Subminiature Toggle Switch, Right Angle Mounting, Vertical Actuation")
      (fields (field (name "PUBLISHER") "Altium Limited"))
      (libsource (lib "mb1045") (part "SW-SPDT"))
    )
    (comp (ref "TP6") (value "VREF") (footprint "TP") (libsource (lib "*") (part "TP")))
    (comp (ref "TP9") (value "VDDA") (footprint "TP") (libsource (lib "*") (part "TP")))
    (comp (ref "U4")
      (value "STM32F4")
      (footprint "BGA216_0R8_13X13_SKT")
      (libsource (lib "MB1165") (part "Manta_Dragon_TFBGA216"))
    )
    (comp (ref "X1")
      (value "25MHz(with socket)")
      (footprint "XTAL_socket")
      (description "Crystal")
      (libsource (lib "*") (part "CRYSTAL"))
    )
    (comp (ref "X2")
      (value "NX3215SA-32.768KHZ-EXS00A-MU00525")
      (footprint "XTAL_2SM_3R2X1R5")
      (description "Crystal")
      (libsource (lib "MB1167") (part "CRYSTAL_32K"))
    )
  )
  (nets
    (net (code "1") (name "+3V3") (class "Default")
      (node (ref "JP10") (pin "1") (pintype "passive"))
      (node (ref "R21") (pin "2") (pinfunction "2_2") (pintype "passive"))
      (node (ref "SW1") (pin "1") (pintype "passive"))
      (node (ref "SW2") (pin "1") (pintype "passive"))
    )
    (net (code "3") (name "/BOOT0") (class "Default")
      (node (ref "JP1") (pin "2") (pinfunction "NO_2") (pintype "passive"))
      (node (ref "R3") (pin "1") (pinfunction "1_1") (pintype "passive"))
      (node (ref "U4") (pin "E6") (pinfunction "BOOT0_E6") (pintype "passive"))
    )
    (net (code "4") (name "/Bootloader_BOOT0") (class "Default")
      (node (ref "D1") (pin "1") (pinfunction "A_1") (pintype "passive"))
    )
    (net (code "5") (name "/Bootloader_RESET") (class "Default")
      (node (ref "JP4") (pin "2") (pinfunction "NO_2") (pintype "passive"))
    )
    (net (code "6") (name "/CAN1_RX") (class "Default")
      (node (ref "JP9") (pin "2") (pinfunction "NO_2") (pintype "passive"))
    )
    (net (code "7") (name "/CAN1_TX") (class "Default")
      (node (ref "SB67") (pin "1") (pinfunction "1_1") (pintype "passive"))
    )
    (net (code "8") (name "/DSI_CK_N") (class "Default")
      (node (ref "U4") (pin "H13") (pinfunction "DSI_CK_N_H13") (pintype "passive"))
    )
    (net (code "9") (name "/DSI_CK_P") (class "Default")
      (node (ref "U4") (pin "H12") (pinfunction "DSI_CK_P_H12") (pintype "passive"))
    )
    (net (code "10") (name "/DSI_D0_N") (class "Default")
      (node (ref "U4") (pin "J13") (pinfunction "DSI_D0_N_J13") (pintype "passive"))
    )
    (net (code "11") (name "/DSI_D0_P") (class "Default")
      (node (ref "U4") (pin "J12") (pinfunction "DSI_D0_P_J12") (pintype "passive"))
    )
    (net (code "12") (name "/DSI_D1_N") (class "Default")
      (node (ref "U4") (pin "F13") (pinfunction "DSI_D1_N_F13") (pintype "passive"))
    )
    (net (code "13") (name "/DSI_D1_P") (class "Default")
      (node (ref "U4") (pin "F12") (pinfunction "DSI_D1_P_F12") (pintype "passive"))
    )
    (net (code "15") (name "/FMC_NWAIT") (class "Default") (node (ref "JP6") (pin "1") (pintype "passive")))
    (net (code "16") (name "/I2S3_SD") (class "Default") (node (ref "JP6") (pin "3") (pintype "passive")))
    (net (code "17") (name "/LCD_BL_CTRL") (class "Default")
      (node (ref "SB80") (pin "1") (pinfunction "1_1") (pintype "passive"))
    )
    (net (code "19") (name "/LCD_G0") (class "Default")
      (node (ref "SB51") (pin "1") (pinfunction "1_1") (pintype "passive"))
    )
    (net (code "20") (name "/LCD_G1") (class "Default")
      (node (ref "SB76") (pin "1") (pinfunction "1_1") (pintype "passive"))
    )
    (net (code "21") (name "/LCD_G5") (class "Default")
      (node (ref "SB57") (pin "2") (pinfunction "2_2") (pintype "passive"))
    )
    (net (code "22") (name "/LCD_G6") (class "Default")
      (node (ref "SB30") (pin "2") (pinfunction "2_2") (pintype "passive"))
    )
    (net (code "23") (name "/LCD_G7") (class "Default")
      (node (ref "SB28") (pin "1") (pinfunction "1_1") (pintype "passive"))
    )
    (net (code "25") (name "/LCD_R0") (class "Default")
      (node (ref "SB8") (pin "2") (pinfunction "2_2") (pintype "passive"))
    )
    (net (code "27") (name "/MC_BusVoltage") (class "Default")
      (node (ref "SB52") (pin "2") (pinfunction "2_2") (pintype "passive"))
    )
    (net (code "28") (name "/MC_CurrentA") (class "Default")
      (node (ref "SB41") (pin "2") (pinfunction "2_2") (pintype "passive"))
    )
    (net (code "29") (name "/MC_CurrentB") (class "Default")
      (node (ref "SB49") (pin "2") (pinfunction "2_2") (pintype "passive"))
    )
    (net (code "30") (name "/MC_CurrentC") (class "Default")
      (node (ref "SB59") (pin "2") (pinfunction "2_2") (pintype "passive"))
    )
    (net (code "31") (name "/MC_DissipativeBrake") (class "Default")
      (node (ref "SB58") (pin "2") (pinfunction "2_2") (pintype "passive"))
    )
    (net (code "32") (name "/MC_EnA") (class "Default")
      (node (ref "SB46") (pin "1") (pinfunction "1_1") (pintype "passive"))
    )
    (net (code "33") (name "/MC_EnB") (class "Default")
      (node (ref "SB33") (pin "1") (pinfunction "1_1") (pintype "passive"))
    )
    (net (code "34") (name "/MC_EnIndex") (class "Default")
      (node (ref "SB42") (pin "1") (pinfunction "1_1") (pintype "passive"))
    )
    (net (code "35") (name "/MC_Heatsink") (class "Default")
      (node (ref "SB69") (pin "2") (pinfunction "2_2") (pintype "passive"))
    )
    (net (code "36") (name "/MC_NTC") (class "Default")
      (node (ref "SB60") (pin "2") (pinfunction "2_2") (pintype "passive"))
    )
    (net (code "37") (name "/MC_PFCpwm") (class "Default")
      (node (ref "SB68") (pin "1") (pinfunction "1_1") (pintype "passive"))
    )
    (net (code "38") (name "/MC_PFCsync1") (class "Default")
      (node (ref "SB75") (pin "1") (pinfunction "1_1") (pintype "passive"))
    )
    (net (code "39") (name "/MC_PFCsync2") (class "Default")
      (node (ref "SB66") (pin "1") (pinfunction "1_1") (pintype "passive"))
    )
    (net (code "40") (name "/MC_UH") (class "Default")
      (node (ref "SB82") (pin "2") (pinfunction "2_2") (pintype "passive"))
    )
    (net (code "41") (name "/MC_UL") (class "Default")
      (node (ref "SB43") (pin "1") (pinfunction "1_1") (pintype "passive"))
    )
    (net (code "42") (name "/MC_VL") (class "Default")
      (node (ref "SB64") (pin "1") (pinfunction "1_1") (pintype "passive"))
    )
    (net (code "43") (name "/MC_WH") (class "Default")
      (node (ref "SB78") (pin "2") (pinfunction "2_2") (pintype "passive"))
    )
    (net (code "44") (name "/MC_WL") (class "Default")
      (node (ref "SB61") (pin "1") (pinfunction "1_1") (pintype "passive"))
    )
    (net (code "45") (name "/MIC_CK") (class "Default")
      (node (ref "R277") (pin "2") (pinfunction "2_2") (pintype "passive"))
    )
    (net (code "46") (name "/MII_COL") (class "Default")
      (node (ref "SB63") (pin "2") (pinfunction "2_2") (pintype "passive"))
    )
    (net (code "47") (name "/MII_CRS") (class "Default")
      (node (ref "SB48") (pin "1") (pinfunction "1_1") (pintype "passive"))
    )
    (net (code "48") (name "/MII_MCO") (class "Default")
      (node (ref "SB77") (pin "1") (pinfunction "1_1") (pintype "passive"))
    )
    (net (code "49") (name "/MII_MDC") (class "Default")
      (node (ref "SB31") (pin "2") (pinfunction "2_2") (pintype "passive"))
    )
    (net (code "50") (name "/MII_MDIO") (class "Default")
      (node (ref "SB40") (pin "1") (pinfunction "1_1") (pintype "passive"))
    )
    (net (code "51") (name "/MII_RXD0") (class "Default")
      (node (ref "SB53") (pin "2") (pinfunction "2_2") (pintype "passive"))
    )
    (net (code "52") (name "/MII_RXD1") (class "Default")
      (node (ref "SB73") (pin "2") (pinfunction "2_2") (pintype "passive"))
    )
    (net (code "53") (name "/MII_RXD2") (class "Default")
      (node (ref "SB55") (pin "2") (pinfunction "2_2") (pintype "passive"))
    )
    (net (code "54") (name "/MII_RX_CLK") (class "Default")
      (node (ref "SB39") (pin "1") (pinfunction "1_1") (pintype "passive"))
    )
    (net (code "55") (name "/MII_RX_DV") (class "Default")
      (node (ref "SB45") (pin "1") (pinfunction "1_1") (pintype "passive"))
    )
    (net (code "56") (name "/MII_RX_ER") (class "Default")
      (node (ref "SB12") (pin "2") (pinfunction "2_2") (pintype "passive"))
    )
    (net (code "57") (name "/MII_TXD0") (class "Default")
      (node (ref "R36") (pin "2") (pinfunction "2_2") (pintype "passive"))
      (node (ref "SB27") (pin "1") (pinfunction "1_1") (pintype "passive"))
    )
    (net (code "58") (name "/MII_TXD1") (class "Default")
      (node (ref "R235") (pin "2") (pinfunction "2_2") (pintype "passive"))
    )
    (net (code "59") (name "/MII_TXD2") (class "Default")
      (node (ref "R233") (pin "2") (pinfunction "2_2") (pintype "passive"))
    )
    (net (code "60") (name "/MII_TXD3") (class "Default")
      (node (ref "R238") (pin "1") (pinfunction "1_1") (pintype "passive"))
    )
    (net (code "61") (name "/MII_TX_CLK") (class "Default")
      (node (ref "SB54") (pin "2") (pinfunction "2_2") (pintype "passive"))
    )
    (net (code "62") (name "/MII_TX_EN") (class "Default")
      (node (ref "R242") (pin "2") (pinfunction "2_2") (pintype "passive"))
    )
    (net (code "63") (name "/PA0") (class "Default")
      (node (ref "SB44") (pin "2") (pinfunction "2_2") (pintype "passive"))
      (node (ref "SB46") (pin "2") (pinfunction "2_2") (pintype "passive"))
      (node (ref "SB48") (pin "2") (pinfunction "2_2") (pintype "passive"))
      (node (ref "U4") (pin "N3") (pinfunction "PA0-WKUP_N3") (pintype "passive"))
    )
    (net (code "64") (name "/PA1") (class "Default")
      (node (ref "SB33") (pin "2") (pinfunction "2_2") (pintype "passive"))
      (node (ref "SB39") (pin "2") (pinfunction "2_2") (pintype "passive"))
      (node (ref "U4") (pin "N2") (pinfunction "PA1_N2") (pintype "passive"))
    )
    (net (code "65") (name "/PA2") (class "Default")
      (node (ref "SB40") (pin "2") (pinfunction "2_2") (pintype "passive"))
      (node (ref "SB42") (pin "2") (pinfunction "2_2") (pintype "passive"))
      (node (ref "U4") (pin "P2") (pinfunction "PA2_P2") (pintype "passive"))
    )
    (net (code "66") (name "/PA4") (class "Default")
      (node (ref "SB47") (pin "2") (pinfunction "2_2") (pintype "passive"))
      (node (ref "U4") (pin "N4") (pinfunction "PA4_N4") (pintype "passive"))
    )
    (net (code "67") (name "/PA5") (class "Default")
      (node (ref "U4") (pin "P4") (pinfunction "PA5_P4") (pintype "passive"))
    )
    (net (code "68") (name "/PA6") (class "Default")
      (node (ref "U4") (pin "P3") (pinfunction "PA6_P3") (pintype "passive"))
    )
    (net (code "69") (name "/PA7") (class "Default")
      (node (ref "SB43") (pin "2") (pinfunction "2_2") (pintype "passive"))
      (node (ref "SB45") (pin "2") (pinfunction "2_2") (pintype "passive"))
      (node (ref "U4") (pin "R3") (pinfunction "PA7_R3") (pintype "passive"))
    )
    (net (code "70") (name "/PA8") (class "Default")
      (node (ref "SB75") (pin "2") (pinfunction "2_2") (pintype "passive"))
      (node (ref "SB77") (pin "2") (pinfunction "2_2") (pintype "passive"))
      (node (ref "SB80") (pin "2") (pinfunction "2_2") (pintype "passive"))
      (node (ref "U4") (pin "F15") (pinfunction "PA8_F15") (pintype "passive"))
    )
    (net (code "71") (name "/PA9") (class "Default")
      (node (ref "R253") (pin "1") (pinfunction "1_1") (pintype "passive"))
      (node (ref "SB72") (pin "2") (pinfunction "2_2") (pintype "passive"))
      (node (ref "U4") (pin "E15") (pinfunction "PA9_E15") (pintype "passive"))
    )
    (net (code "72") (name "/PA10") (class "Default")
      (node (ref "U4") (pin "D15") (pinfunction "PA10_D15") (pintype "passive"))
    )
    (net (code "73") (name "/PA11") (class "Default")
      (node (ref "JP9") (pin "1") (pinfunction "COMMON_1") (pintype "passive"))
      (node (ref "SB68") (pin "2") (pinfunction "2_2") (pintype "passive"))
      (node (ref "U4") (pin "C15") (pinfunction "PA11_C15") (pintype "passive"))
    )
    (net (code "74") (name "/PA12") (class "Default")
      (node (ref "SB66") (pin "2") (pinfunction "2_2") (pintype "passive"))
      (node (ref "SB67") (pin "2") (pinfunction "2_2") (pintype "passive"))
      (node (ref "SB71") (pin "2") (pinfunction "2_2") (pintype "passive"))
      (node (ref "U4") (pin "B15") (pinfunction "PA12_B15") (pintype "passive"))
    )
    (net (code "75") (name "/PA13") (class "Default")
      (node (ref "U4") (pin "A15") (pinfunction "PA13_A15") (pintype "passive"))
    )
    (net (code "76") (name "/PA14") (class "Default")
      (node (ref "U4") (pin "A14") (pinfunction "PA14_A14") (pintype "passive"))
    )
    (net (code "77") (name "/PA15") (class "Default")
      (node (ref "U4") (pin "A13") (pinfunction "PA15_A13") (pintype "passive"))
    )
    (net (code "78") (name "/PAR_D0") (class "Default")
      (node (ref "JP5") (pin "3") (pintype "passive"))
      (node (ref "SB82") (pin "1") (pinfunction "1_1") (pintype "passive"))
      (node (ref "U4") (pin "H15") (pinfunction "PC6_H15") (pintype "passive"))
    )
    (net (code "79") (name "/PAR_D1") (class "Default")
      (node (ref "R277") (pin "1") (pinfunction "1_1") (pintype "passive"))
      (node (ref "U4") (pin "G15") (pinfunction "PC7_G15") (pintype "passive"))
    )
    (net (code "80") (name "/PAR_D2") (class "Default")
      (node (ref "SB78") (pin "1") (pinfunction "1_1") (pintype "passive"))
      (node (ref "SB81") (pin "1") (pinfunction "1_1") (pintype "passive"))
      (node (ref "U4") (pin "G14") (pinfunction "PC8_G14") (pintype "passive"))
    )
    (net (code "81") (name "/PAR_D3") (class "Default")
      (node (ref "R252") (pin "2") (pinfunction "2_2") (pintype "passive"))
      (node (ref "U4") (pin "F14") (pinfunction "PC9_F14") (pintype "passive"))
    )
    (net (code "82") (name "/PAR_D4") (class "Default")
      (node (ref "R272") (pin "2") (pinfunction "2_2") (pintype "passive"))
      (node (ref "U4") (pin "B13") (pinfunction "PC11_B13") (pintype "passive"))
    )
    (net (code "83") (name "/PAR_D5") (class "Default")
      (node (ref "U4") (pin "C11") (pinfunction "PD3_C11") (pintype "passive"))
    )
    (net (code "84") (name "/PAR_D6") (class "Default")
      (node (ref "SB4") (pin "1") (pinfunction "1_1") (pintype "passive"))
    )
    (net (code "85") (name "/PAR_D7") (class "Default")
      (node (ref "SB17") (pin "1") (pinfunction "1_1") (pintype "passive"))
    )
    (net (code "86") (name "/PAR_D8") (class "Default")
      (node (ref "R278") (pin "2") (pinfunction "2_2") (pintype "passive"))
      (node (ref "U4") (pin "B14") (pinfunction "PC10_B14") (pintype "passive"))
    )
    (net (code "87") (name "/PAR_D9") (class "Default")
      (node (ref "U4") (pin "A12") (pinfunction "PC12_A12") (pintype "passive"))
    )
    (net (code "88") (name "/PAR_D10") (class "Default")
      (node (ref "JP6") (pin "2") (pintype "passive"))
      (node (ref "U4") (pin "B11") (pinfunction "PD6_B11") (pintype "passive"))
    )
    (net (code "89") (name "/PAR_D11") (class "Default")
      (node (ref "SB83") (pin "2") (pinfunction "2_2") (pintype "passive"))
      (node (ref "U4") (pin "D12") (pinfunction "PD2_D12") (pintype "passive"))
    )
    (net (code "91") (name "/PAR_HSYNC") (class "Default")
      (node (ref "SB47") (pin "1") (pinfunction "1_1") (pintype "passive"))
    )
    (net (code "93") (name "/PB0") (class "Default")
      (node (ref "SB76") (pin "2") (pinfunction "2_2") (pintype "passive"))
      (node (ref "SB79") (pin "2") (pinfunction "2_2") (pintype "passive"))
      (node (ref "U4") (pin "R5") (pinfunction "PB0_R5") (pintype "passive"))
    )
    (net (code "94") (name "/PB1") (class "Default")
      (node (ref "SB50") (pin "2") (pinfunction "2_2") (pintype "passive"))
      (node (ref "SB51") (pin "2") (pinfunction "2_2") (pintype "passive"))
      (node (ref "U4") (pin "R4") (pinfunction "PB1_R4") (pintype "passive"))
    )
    (net (code "95") (name "/PB2") (class "Default")
      (node (ref "R6") (pin "2") (pinfunction "2_2") (pintype "passive"))
      (node (ref "U4") (pin "M5") (pinfunction "PB2_M5") (pintype "passive"))
    )
    (net (code "96") (name "/PB3") (class "Default")
      (node (ref "JP5") (pin "2") (pintype "passive"))
      (node (ref "U4") (pin "A10") (pinfunction "PB3_A10") (pintype "passive"))
    )
    (net (code "97") (name "/PB4") (class "Default")
      (node (ref "U4") (pin "A9") (pinfunction "PB4_A9") (pintype "passive"))
    )
    (net (code "98") (name "/PB5") (class "Default")
      (node (ref "SB28") (pin "2") (pinfunction "2_2") (pintype "passive"))
      (node (ref "SB29") (pin "2") (pinfunction "2_2") (pintype "passive"))
      (node (ref "U4") (pin "A8") (pinfunction "PB5_A8") (pintype "passive"))
    )
    (net (code "99") (name "/PB6") (class "Default")
      (node (ref "R40") (pin "2") (pinfunction "2_2") (pintype "passive"))
    )
    (net (code "100") (name "/PB7") (class "Default")
      (node (ref "U4") (pin "B5") (pinfunction "PB7_B5") (pintype "passive"))
    )
    (net (code "101") (name "/PB8") (class "Default")
      (node (ref "U4") (pin "A7") (pinfunction "PB8_A7") (pintype "passive"))
    )
    (net (code "102") (name "/PB9") (class "Default")
      (node (ref "U4") (pin "B4") (pinfunction "PB9_B4") (pintype "passive"))
    )
    (net (code "103") (name "/PB12") (class "Default")
      (node (ref "R254") (pin "2") (pinfunction "2_2") (pintype "passive"))
      (node (ref "SB70") (pin "2") (pinfunction "2_2") (pintype "passive"))
      (node (ref "SB74") (pin "2") (pinfunction "2_2") (pintype "passive"))
      (node (ref "U4") (pin "L13") (pinfunction "PB12_L13") (pintype "passive"))
    )
    (net (code "104") (name "/PB14") (class "Default")
      (node (ref "SB64") (pin "2") (pinfunction "2_2") (pintype "passive"))
      (node (ref "SB65") (pin "2") (pinfunction "2_2") (pintype "passive"))
      (node (ref "U4") (pin "R14") (pinfunction "PB14_R14") (pintype "passive"))
    )
    (net (code "105") (name "/PB15") (class "Default")
      (node (ref "SB61") (pin "2") (pinfunction "2_2") (pintype "passive"))
      (node (ref "SB62") (pin "2") (pinfunction "2_2") (pintype "passive"))
      (node (ref "U4") (pin "R15") (pinfunction "PB15_R15") (pintype "passive"))
    )
    (net (code "107") (name "/PC0") (class "Default")
      (node (ref "SB34") (pin "1") (pinfunction "1_1") (pintype "passive"))
      (node (ref "U4") (pin "M2") (pinfunction "PC0_M2") (pintype "passive"))
    )
    (net (code "108") (name "/PC1") (class "Default")
      (node (ref "SB31") (pin "1") (pinfunction "1_1") (pintype "passive"))
      (node (ref "SB41") (pin "1") (pinfunction "1_1") (pintype "passive"))
      (node (ref "U4") (pin "M3") (pinfunction "PC1_M3") (pintype "passive"))
    )
    (net (code "109") (name "/PC2") (class "Default")
      (node (ref "R233") (pin "1") (pinfunction "1_1") (pintype "passive"))
      (node (ref "SB49") (pin "1") (pinfunction "1_1") (pintype "passive"))
      (node (ref "U4") (pin "M4") (pinfunction "PC2_M4") (pintype "passive"))
    )
    (net (code "110") (name "/PC3") (class "Default")
      (node (ref "SB54") (pin "1") (pinfunction "1_1") (pintype "passive"))
      (node (ref "SB59") (pin "1") (pinfunction "1_1") (pintype "passive"))
      (node (ref "U4") (pin "L4") (pinfunction "PC3_L4") (pintype "passive"))
    )
    (net (code "111") (name "/PC4") (class "Default")
      (node (ref "SB52") (pin "1") (pinfunction "1_1") (pintype "passive"))
      (node (ref "SB53") (pin "1") (pinfunction "1_1") (pintype "passive"))
      (node (ref "U4") (pin "N5") (pinfunction "PC4_N5") (pintype "passive"))
    )
    (net (code "112") (name "/PC5") (class "Default")
      (node (ref "SB69") (pin "1") (pinfunction "1_1") (pintype "passive"))
      (node (ref "SB73") (pin "1") (pinfunction "1_1") (pintype "passive"))
      (node (ref "U4") (pin "P5") (pinfunction "PC5_P5") (pintype "passive"))
    )
    (net (code "113") (name "/PC13") (class "Default")
      (node (ref "U4") (pin "D1") (pinfunction "PC13-ANTI_TAMP_D1") (pintype "passive"))
    )
    (net (code "114") (name "/PC14") (class "Default")
      (node (ref "R19") (pin "2") (pinfunction "2_2") (pintype "passive"))
      (node (ref "U4") (pin "E1") (pinfunction "PC14-OSC32_IN_E1") (pintype "passive"))
    )
    (net (code "115") (name "/PC15") (class "Default")
      (node (ref "R18") (pin "2") (pinfunction "2_2") (pintype "passive"))
      (node (ref "U4") (pin "F1") (pinfunction "PC15-OSC32_OUT_F1") (pintype "passive"))
    )
    (net (code "117") (name "/PD0") (class "Default")
      (node (ref "R262") (pin "2") (pinfunction "2_2") (pintype "passive"))
    )
    (net (code "118") (name "/PD1") (class "Default")
      (node (ref "R273") (pin "2") (pinfunction "2_2") (pintype "passive"))
    )
    (net (code "119") (name "/PD4") (class "Default")
      (node (ref "U4") (pin "D11") (pinfunction "PD4_D11") (pintype "passive"))
    )
    (net (code "120") (name "/PD5") (class "Default")
      (node (ref "U4") (pin "C10") (pinfunction "PD5_C10") (pintype "passive"))
    )
    (net (code "121") (name "/PD7") (class "Default")
      (node (ref "U4") (pin "A11") (pinfunction "PD7_A11") (pintype "passive"))
    )
    (net (code "122") (name "/PD8") (class "Default")
      (node (ref "R56") (pin "2") (pinfunction "2_2") (pintype "passive"))
    )
    (net (code "123") (name "/PD9") (class "Default")
      (node (ref "R65") (pin "2") (pinfunction "2_2") (pintype "passive"))
    )
    (net (code "124") (name "/PD10") (class "Default")
      (node (ref "R66") (pin "2") (pinfunction "2_2") (pintype "passive"))
    )
    (net (code "125") (name "/PD11") (class "Default")
      (node (ref "R260") (pin "1") (pinfunction "1_1") (pintype "passive"))
    )
    (net (code "126") (name "/PD12") (class "Default")
      (node (ref "R271") (pin "2") (pinfunction "2_2") (pintype "passive"))
    )
    (net (code "127") (name "/PD13") (class "Default")
      (node (ref "R258") (pin "2") (pinfunction "2_2") (pintype "passive"))
    )
    (net (code "128") (name "/PD14") (class "Default")
      (node (ref "R268") (pin "2") (pinfunction "2_2") (pintype "passive"))
    )
    (net (code "129") (name "/PD15") (class "Default")
      (node (ref "R256") (pin "2") (pinfunction "2_2") (pintype "passive"))
    )
    (net (code "131") (name "/PE0") (class "Default")
      (node (ref "U4") (pin "A6") (pinfunction "PE0_A6") (pintype "passive"))
    )
    (net (code "132") (name "/PE1") (class "Default")
      (node (ref "U4") (pin "A5") (pinfunction "PE1_A5") (pintype "passive"))
    )
    (net (code "133") (name "/PE2") (class "Default")
      (node (ref "R38") (pin "2") (pinfunction "2_2") (pintype "passive"))
      (node (ref "R39") (pin "2") (pinfunction "2_2") (pintype "passive"))
    )
    (net (code "134") (name "/PE3") (class "Default")
      (node (ref "R234") (pin "2") (pinfunction "2_2") (pintype "passive"))
      (node (ref "R37") (pin "2") (pinfunction "2_2") (pintype "passive"))
    )
    (net (code "135") (name "/PE4") (class "Default")
      (node (ref "R231") (pin "2") (pinfunction "2_2") (pintype "passive"))
      (node (ref "R35") (pin "2") (pinfunction "2_2") (pintype "passive"))
    )
    (net (code "136") (name "/PE5") (class "Default")
      (node (ref "R24") (pin "2") (pinfunction "2_2") (pintype "passive"))
      (node (ref "R32") (pin "2") (pinfunction "2_2") (pintype "passive"))
    )
    (net (code "137") (name "/PE6") (class "Default")
      (node (ref "R229") (pin "2") (pinfunction "2_2") (pintype "passive"))
      (node (ref "R34") (pin "2") (pinfunction "2_2") (pintype "passive"))
    )
    (net (code "138") (name "/PE7") (class "Default")
      (node (ref "R58") (pin "2") (pinfunction "2_2") (pintype "passive"))
    )
    (net (code "139") (name "/PE8") (class "Default")
      (node (ref "R50") (pin "2") (pinfunction "2_2") (pintype "passive"))
    )
    (net (code "140") (name "/PE9") (class "Default")
      (node (ref "R49") (pin "2") (pinfunction "2_2") (pintype "passive"))
    )
    (net (code "141") (name "/PE10") (class "Default")
      (node (ref "R59") (pin "2") (pinfunction "2_2") (pintype "passive"))
    )
    (net (code "142") (name "/PE11") (class "Default")
      (node (ref "R51") (pin "2") (pinfunction "2_2") (pintype "passive"))
    )
    (net (code "143") (name "/PE12") (class "Default")
      (node (ref "R60") (pin "2") (pinfunction "2_2") (pintype "passive"))
    )
    (net (code "144") (name "/PE13") (class "Default")
      (node (ref "R62") (pin "2") (pinfunction "2_2") (pintype "passive"))
    )
    (net (code "145") (name "/PE14") (class "Default")
      (node (ref "R52") (pin "2") (pinfunction "2_2") (pintype "passive"))
    )
    (net (code "146") (name "/PE15") (class "Default")
      (node (ref "R61") (pin "2") (pinfunction "2_2") (pintype "passive"))
    )
    (net (code "148") (name "/PF0") (class "Default")
      (node (ref "R236") (pin "2") (pinfunction "2_2") (pintype "passive"))
    )
    (net (code "149") (name "/PF1") (class "Default")
      (node (ref "R232") (pin "2") (pinfunction "2_2") (pintype "passive"))
    )
    (net (code "150") (name "/PF2") (class "Default")
      (node (ref "R230") (pin "2") (pinfunction "2_2") (pintype "passive"))
    )
    (net (code "151") (name "/PF3") (class "Default")
      (node (ref "R226") (pin "2") (pinfunction "2_2") (pintype "passive"))
    )
    (net (code "152") (name "/PF4") (class "Default")
      (node (ref "R223") (pin "2") (pinfunction "2_2") (pintype "passive"))
    )
    (net (code "153") (name "/PF5") (class "Default")
      (node (ref "R221") (pin "2") (pinfunction "2_2") (pintype "passive"))
    )
    (net (code "154") (name "/PF6") (class "Default")
      (node (ref "R25") (pin "2") (pinfunction "2_2") (pintype "passive"))
    )
    (net (code "155") (name "/PF7") (class "Default")
      (node (ref "R23") (pin "2") (pinfunction "2_2") (pintype "passive"))
    )
    (net (code "156") (name "/PF8") (class "Default")
      (node (ref "R237") (pin "2") (pinfunction "2_2") (pintype "passive"))
    )
    (net (code "157") (name "/PF9") (class "Default")
      (node (ref "R27") (pin "2") (pinfunction "2_2") (pintype "passive"))
    )
    (net (code "158") (name "/PF10") (class "Default")
      (node (ref "R222") (pin "2") (pinfunction "2_2") (pintype "passive"))
    )
    (net (code "159") (name "/PF11") (class "Default")
      (node (ref "R48") (pin "2") (pinfunction "2_2") (pintype "passive"))
    )
    (net (code "160") (name "/PF12") (class "Default")
      (node (ref "R248") (pin "2") (pinfunction "2_2") (pintype "passive"))
    )
    (net (code "161") (name "/PF13") (class "Default")
      (node (ref "R245") (pin "2") (pinfunction "2_2") (pintype "passive"))
    )
    (net (code "162") (name "/PF14") (class "Default")
      (node (ref "R249") (pin "2") (pinfunction "2_2") (pintype "passive"))
    )
    (net (code "163") (name "/PF15") (class "Default")
      (node (ref "R261") (pin "2") (pinfunction "2_2") (pintype "passive"))
    )
    (net (code "165") (name "/PG0") (class "Default")
      (node (ref "R251") (pin "2") (pinfunction "2_2") (pintype "passive"))
    )
    (net (code "166") (name "/PG1") (class "Default")
      (node (ref "R250") (pin "2") (pinfunction "2_2") (pintype "passive"))
    )
    (net (code "167") (name "/PG2") (class "Default")
      (node (ref "R269") (pin "2") (pinfunction "2_2") (pintype "passive"))
    )
    (net (code "168") (name "/PG3") (class "Default")
      (node (ref "R257") (pin "2") (pinfunction "2_2") (pintype "passive"))
    )
    (net (code "169") (name "/PG4") (class "Default")
      (node (ref "R270") (pin "2") (pinfunction "2_2") (pintype "passive"))
    )
    (net (code "170") (name "/PG5") (class "Default")
      (node (ref "R259") (pin "2") (pinfunction "2_2") (pintype "passive"))
    )
    (net (code "171") (name "/PG6") (class "Default")
      (node (ref "U4") (pin "J15") (pinfunction "PG6_J15") (pintype "passive"))
    )
    (net (code "172") (name "/PG7") (class "Default")
      (node (ref "U4") (pin "J14") (pinfunction "PG7_J14") (pintype "passive"))
    )
    (net (code "173") (name "/PG8") (class "Default")
      (node (ref "R267") (pin "2") (pinfunction "2_2") (pintype "passive"))
    )
    (net (code "174") (name "/PG9") (class "Default")
      (node (ref "U4") (pin "D9") (pinfunction "PG9_D9") (pintype "passive"))
    )
    (net (code "175") (name "/PG10") (class "Default")
      (node (ref "U4") (pin "C8") (pinfunction "PG10_C8") (pintype "passive"))
    )
    (net (code "176") (name "/PG11") (class "Default")
      (node (ref "R242") (pin "1") (pinfunction "1_1") (pintype "passive"))
      (node (ref "SB60") (pin "1") (pinfunction "1_1") (pintype "passive"))
      (node (ref "U4") (pin "B8") (pinfunction "PG11_B8") (pintype "passive"))
    )
    (net (code "177") (name "/PG12") (class "Default")
      (node (ref "U4") (pin "C7") (pinfunction "PG12_C7") (pintype "passive"))
    )
    (net (code "178") (name "/PG13") (class "Default")
      (node (ref "R36") (pin "1") (pinfunction "1_1") (pintype "passive"))
      (node (ref "SB8") (pin "1") (pinfunction "1_1") (pintype "passive"))
      (node (ref "U4") (pin "B3") (pinfunction "PG13_B3") (pintype "passive"))
    )
    (net (code "179") (name "/PG14") (class "Default")
      (node (ref "R235") (pin "1") (pinfunction "1_1") (pintype "passive"))
      (node (ref "U4") (pin "A4") (pinfunction "PG14_A4") (pintype "passive"))
    )
    (net (code "180") (name "/PG15") (class "Default")
      (node (ref "R41") (pin "2") (pinfunction "2_2") (pintype "passive"))
    )
    (net (code "182") (name "/PH0") (class "Default")
      (node (ref "R20") (pin "1") (pinfunction "1_1") (pintype "passive"))
      (node (ref "U4") (pin "G1") (pinfunction "PH0-OSC_IN_G1") (pintype "passive"))
    )
    (net (code "183") (name "/PH1") (class "Default")
      (node (ref "C23") (pin "1") (pinfunction "1_1") (pintype "passive"))
      (node (ref "U4") (pin "H1") (pinfunction "PH1-OSC_OUT_H1") (pintype "passive"))
      (node (ref "X1") (pin "1") (pinfunction "1_1") (pintype "passive"))
    )
    (net (code "184") (name "/PH2") (class "Default")
      (node (ref "U4") (pin "K4") (pinfunction "PH2_K4") (pintype "passive"))
    )
    (net (code "185") (name "/PH3") (class "Default")
      (node (ref "R243") (pin "1") (pinfunction "1_1") (pintype "passive"))
    )
    (net (code "186") (name "/PH4") (class "Default")
      (node (ref "SB56") (pin "1") (pinfunction "1_1") (pintype "passive"))
      (node (ref "SB57") (pin "1") (pinfunction "1_1") (pintype "passive"))
      (node (ref "U4") (pin "H4") (pinfunction "PH4_H4") (pintype "passive"))
    )
    (net (code "187") (name "/PH5") (class "Default")
      (node (ref "R246") (pin "1") (pinfunction "1_1") (pintype "passive"))
    )
    (net (code "188") (name "/PH6") (class "Default")
      (node (ref "SB55") (pin "1") (pinfunction "1_1") (pintype "passive"))
      (node (ref "SB58") (pin "1") (pinfunction "1_1") (pintype "passive"))
      (node (ref "U4") (pin "P13") (pinfunction "PH6_P13") (pintype "passive"))
    )
    (net (code "189") (name "/PH7") (class "Default")
      (node (ref "U4") (pin "N13") (pinfunction "PH7_N13") (pintype "passive"))
    )
    (net (code "190") (name "/PH8") (class "Default")
      (node (ref "R53") (pin "1") (pinfunction "1_1") (pintype "passive"))
    )
    (net (code "191") (name "/PH9") (class "Default")
      (node (ref "R54") (pin "1") (pinfunction "1_1") (pintype "passive"))
    )
    (net (code "192") (name "/PH10") (class "Default")
      (node (ref "R63") (pin "1") (pinfunction "1_1") (pintype "passive"))
    )
    (net (code "193") (name "/PH11") (class "Default")
      (node (ref "R64") (pin "1") (pinfunction "1_1") (pintype "passive"))
    )
    (net (code "194") (name "/PH12") (class "Default")
      (node (ref "R55") (pin "1") (pinfunction "1_1") (pintype "passive"))
    )
    (net (code "195") (name "/PH13") (class "Default")
      (node (ref "R266") (pin "1") (pinfunction "1_1") (pintype "passive"))
    )
    (net (code "196") (name "/PH14") (class "Default")
      (node (ref "R276") (pin "1") (pinfunction "1_1") (pintype "passive"))
    )
    (net (code "197") (name "/PH15") (class "Default")
      (node (ref "R275") (pin "1") (pinfunction "1_1") (pintype "passive"))
    )
    (net (code "199") (name "/PI0") (class "Default")
      (node (ref "R265") (pin "1") (pinfunction "1_1") (pintype "passive"))
    )
    (net (code "200") (name "/PI1") (class "Default")
      (node (ref "R264") (pin "1") (pinfunction "1_1") (pintype "passive"))
    )
    (net (code "201") (name "/PI2") (class "Default")
      (node (ref "R263") (pin "1") (pinfunction "1_1") (pintype "passive"))
    )
    (net (code "202") (name "/PI3") (class "Default")
      (node (ref "R274") (pin "1") (pinfunction "1_1") (pintype "passive"))
    )
    (net (code "203") (name "/PI4") (class "Default")
      (node (ref "U4") (pin "C3") (pinfunction "PI4_C3") (pintype "passive"))
    )
    (net (code "204") (name "/PI5") (class "Default")
      (node (ref "U4") (pin "D3") (pinfunction "PI5_D3") (pintype "passive"))
    )
    (net (code "205") (name "/PI6") (class "Default")
      (node (ref "R247") (pin "1") (pinfunction "1_1") (pintype "passive"))
    )
    (net (code "206") (name "/PI7") (class "Default")
      (node (ref "R240") (pin "1") (pinfunction "1_1") (pintype "passive"))
    )
    (net (code "207") (name "/PI8") (class "Default")
      (node (ref "U4") (pin "C2") (pinfunction "PI8-ANTI_TAMP2_C2") (pintype "passive"))
    )
    (net (code "208") (name "/PI9") (class "Default")
      (node (ref "R241") (pin "1") (pinfunction "1_1") (pintype "passive"))
    )
    (net (code "209") (name "/PI10") (class "Default")
      (node (ref "R244") (pin "1") (pinfunction "1_1") (pintype "passive"))
    )
    (net (code "210") (name "/PI11") (class "Default")
      (node (ref "SB30") (pin "1") (pinfunction "1_1") (pintype "passive"))
      (node (ref "SB32") (pin "1") (pinfunction "1_1") (pintype "passive"))
      (node (ref "U4") (pin "F3") (pinfunction "PI11_F3") (pintype "passive"))
    )
    (net (code "211") (name "/PI12") (class "Default")
      (node (ref "U4") (pin "E3") (pinfunction "PI12_E3") (pintype "passive"))
    )
    (net (code "212") (name "/PI13") (class "Default")
      (node (ref "U4") (pin "G3") (pinfunction "PI13_G3") (pintype "passive"))
    )
    (net (code "213") (name "/PI14") (class "Default")
      (node (ref "R214") (pin "1") (pinfunction "1_1") (pintype "passive"))
    )
    (net (code "214") (name "/PI15") (class "Default")
      (node (ref "U4") (pin "G4") (pinfunction "PI15_G4") (pintype "passive"))
    )
    (net (code "216") (name "/PJ0") (class "Default")
      (node (ref "U4") (pin "R6") (pinfunction "PJ0_R6") (pintype "passive"))
    )
    (net (code "217") (name "/PJ1") (class "Default")
      (node (ref "U4") (pin "R7") (pinfunction "PJ1_R7") (pintype "passive"))
    )
    (net (code "218") (name "/PJ2") (class "Default")
      (node (ref "U4") (pin "P7") (pinfunction "PJ2_P7") (pintype "passive"))
    )
    (net (code "219") (name "/PJ3") (class "Default")
      (node (ref "U4") (pin "N8") (pinfunction "PJ3_N8") (pintype "passive"))
    )
    (net (code "220") (name "/PJ4") (class "Default")
      (node (ref "U4") (pin "M9") (pinfunction "PJ4_M9") (pintype "passive"))
    )
    (net (code "221") (name "/PJ5") (class "Default")
      (node (ref "U4") (pin "M14") (pinfunction "PJ5_M14") (pintype "passive"))
    )
    (net (code "222") (name "/PJ12") (class "Default")
      (node (ref "U4") (pin "B10") (pinfunction "PJ12_B10") (pintype "passive"))
    )
    (net (code "223") (name "/PJ13") (class "Default")
      (node (ref "U4") (pin "B9") (pinfunction "PJ13_B9") (pintype "passive"))
    )
    (net (code "224") (name "/PJ14") (class "Default")
      (node (ref "U4") (pin "C9") (pinfunction "PJ14_C9") (pintype "passive"))
    )
    (net (code "225") (name "/PJ15") (class "Default")
      (node (ref "U4") (pin "D10") (pinfunction "PJ15_D10") (pintype "passive"))
    )
    (net (code "228") (name "/PK3") (class "Default")
      (node (ref "U4") (pin "D8") (pinfunction "PK3_D8") (pintype "passive"))
    )
    (net (code "229") (name "/PK4") (class "Default")
      (node (ref "U4") (pin "D7") (pinfunction "PK4_D7") (pintype "passive"))
    )
    (net (code "230") (name "/PK5") (class "Default")
      (node (ref "U4") (pin "C6") (pinfunction "PK5_C6") (pintype "passive"))
    )
    (net (code "231") (name "/PK6") (class "Default")
      (node (ref "U4") (pin "C5") (pinfunction "PK6_C5") (pintype "passive"))
    )
    (net (code "232") (name "/PK7") (class "Default")
      (node (ref "U4") (pin "C4") (pinfunction "PK7_C4") (pintype "passive"))
    )
    (net (code "234") (name "/RESET#") (class "Default")
      (node (ref "B1") (pin "2") (pinfunction "B0_2") (pintype "passive"))
      (node (ref "B1") (pin "3") (pinfunction "B1_3") (pintype "passive"))
      (node (ref "C102") (pin "2") (pinfunction "2_2") (pintype "passive"))
      (node (ref "D2") (pin "1") (pinfunction "A_1") (pintype "passive"))
      (node (ref "U4") (pin "J1") (pinfunction "NRST_J1") (pintype "passive"))
    )
    (net (code "235") (name "/RS232{slash}IrDA_TX") (class "Default")
      (node (ref "SB72") (pin "1") (pinfunction "1_1") (pintype "passive"))
    )
    (net (code "236") (name "/SAI1_FSA") (class "Default")
      (node (ref "SB7") (pin "1") (pinfunction "1_1") (pintype "passive"))
    )
    (net (code "237") (name "/SAI1_SCKA") (class "Default")
      (node (ref "SB5") (pin "1") (pinfunction "1_1") (pintype "passive"))
    )
    (net (code "238") (name "/SAI1_SDA") (class "Default")
      (node (ref "SB19") (pin "1") (pinfunction "1_1") (pintype "passive"))
    )
    (net (code "239") (name "/SAI1_SDB") (class "Default")
      (node (ref "SB9") (pin "1") (pinfunction "1_1") (pintype "passive"))
    )
    (net (code "240") (name "/TDO{slash}SWO") (class "Default")
      (node (ref "JP5") (pin "1") (pintype "passive"))
    )
    (net (code "241") (name "/TRACE_CK") (class "Default")
      (node (ref "SB11") (pin "1") (pinfunction "1_1") (pintype "passive"))
    )
    (net (code "242") (name "/TRACE_D0") (class "Default")
      (node (ref "SB10") (pin "1") (pinfunction "1_1") (pintype "passive"))
    )
    (net (code "243") (name "/TRACE_D1") (class "Default")
      (node (ref "SB6") (pin "1") (pinfunction "1_1") (pintype "passive"))
    )
    (net (code "244") (name "/TRACE_D2") (class "Default")
      (node (ref "SB3") (pin "1") (pinfunction "1_1") (pintype "passive"))
    )
    (net (code "245") (name "/TRACE_D3") (class "Default")
      (node (ref "SB18") (pin "1") (pinfunction "1_1") (pintype "passive"))
    )
    (net (code "246") (name "/ULPI_D0") (class "Default")
      (node (ref "U4") (pin "R2") (pinfunction "PA3_R2") (pintype "passive"))
    )
    (net (code "247") (name "/ULPI_D1") (class "Default")
      (node (ref "SB79") (pin "1") (pinfunction "1_1") (pintype "passive"))
    )
    (net (code "248") (name "/ULPI_D2") (class "Default")
      (node (ref "SB50") (pin "1") (pinfunction "1_1") (pintype "passive"))
    )
    (net (code "249") (name "/ULPI_D3") (class "Default")
      (node (ref "U4") (pin "P12") (pinfunction "PB10_P12") (pintype "passive"))
    )
    (net (code "250") (name "/ULPI_D4") (class "Default")
      (node (ref "U4") (pin "R13") (pinfunction "PB11_R13") (pintype "passive"))
    )
    (net (code "251") (name "/ULPI_D5") (class "Default")
      (node (ref "SB74") (pin "1") (pinfunction "1_1") (pintype "passive"))
    )
    (net (code "252") (name "/ULPI_D6") (class "Default")
      (node (ref "R255") (pin "2") (pinfunction "2_2") (pintype "passive"))
      (node (ref "U4") (pin "K14") (pinfunction "PB13_K14") (pintype "passive"))
    )
    (net (code "253") (name "/ULPI_D7") (class "Default")
      (node (ref "SB29") (pin "1") (pinfunction "1_1") (pintype "passive"))
    )
    (net (code "254") (name "/ULPI_DIR") (class "Default")
      (node (ref "SB32") (pin "2") (pinfunction "2_2") (pintype "passive"))
    )
    (net (code "256") (name "/ULPI_NXT") (class "Default")
      (node (ref "SB56") (pin "2") (pinfunction "2_2") (pintype "passive"))
    )
    (net (code "257") (name "/ULPI_STP") (class "Default")
      (node (ref "SB34") (pin "2") (pinfunction "2_2") (pintype "passive"))
    )
    (net (code "258") (name "/USB_FS1_DP") (class "Default")
      (node (ref "SB71") (pin "1") (pinfunction "1_1") (pintype "passive"))
    )
    (net (code "259") (name "/USB_FS2_DM") (class "Default")
      (node (ref "SB65") (pin "1") (pinfunction "1_1") (pintype "passive"))
    )
    (net (code "260") (name "/USB_FS2_DP") (class "Default")
      (node (ref "SB62") (pin "1") (pinfunction "1_1") (pintype "passive"))
    )
    (net (code "261") (name "/USB_FS2_ID") (class "Default")
      (node (ref "SB70") (pin "1") (pinfunction "1_1") (pintype "passive"))
    )
    (net (code "262") (name "/WAKEUP") (class "Default")
      (node (ref "SB44") (pin "1") (pinfunction "1_1") (pintype "passive"))
    )
    (net (code "263") (name "/uSD_CMD") (class "Default")
      (node (ref "SB83") (pin "1") (pinfunction "1_1") (pintype "passive"))
    )
    (net (code "264") (name "/uSD_D0") (class "Default")
      (node (ref "SB81") (pin "2") (pinfunction "2_2") (pintype "passive"))
    )
    (net (code "265") (name "/uSD_D1") (class "Default")
      (node (ref "R252") (pin "1") (pinfunction "1_1") (pintype "passive"))
    )
    (net (code "266") (name "/uSD_D2") (class "Default")
      (node (ref "R278") (pin "1") (pinfunction "1_1") (pintype "passive"))
    )
    (net (code "267") (name "/uSD_D3") (class "Default")
      (node (ref "R272") (pin "1") (pinfunction "1_1") (pintype "passive"))
    )
    (net (code "268") (name "DSI_VDD12") (class "Default")
      (node (ref "C140") (pin "1") (pinfunction "1_1") (pintype "passive"))
      (node (ref "C141") (pin "1") (pinfunction "1_1") (pintype "passive"))
      (node (ref "C31") (pin "1") (pinfunction "1_1") (pintype "passive"))
      (node (ref "U4") (pin "G13") (pinfunction "DSI_VDD12_G13") (pintype "passive"))
      (node (ref "U4") (pin "K12") (pinfunction "DSI_VCAP_K12") (pintype "passive"))
    )
    (net (code "269") (name "GND") (class "Default")
      (node (ref "B1") (pin "1") (pinfunction "A0_1") (pintype "passive"))
      (node (ref "B1") (pin "4") (pinfunction "A1_4") (pintype "passive"))
      (node (ref "BT1") (pin "2") (pinfunction "-_2") (pintype "passive"))
      (node (ref "C102") (pin "1") (pinfunction "1_1") (pintype "passive"))
      (node (ref "C108") (pin "2") (pinfunction "2_2") (pintype "passive"))
      (node (ref "C109") (pin "2") (pinfunction "2_2") (pintype "passive"))
      (node (ref "C111") (pin "2") (pinfunction "2_2") (pintype "passive"))
      (node (ref "C112") (pin "2") (pinfunction "2_2") (pintype "passive"))
      (node (ref "C113") (pin "1") (pinfunction "1_1") (pintype "passive"))
      (node (ref "C114") (pin "2") (pinfunction "2_2") (pintype "passive"))
      (node (ref "C115") (pin "2") (pinfunction "2_2") (pintype "passive"))
      (node (ref "C116") (pin "1") (pinfunction "1_1") (pintype "passive"))
      (node (ref "C117") (pin "2") (pinfunction "2_2") (pintype "passive"))
      (node (ref "C118") (pin "2") (pinfunction "2_2") (pintype "passive"))
      (node (ref "C119") (pin "2") (pinfunction "2_2") (pintype "passive"))
      (node (ref "C120") (pin "2") (pinfunction "2_2") (pintype "passive"))
      (node (ref "C121") (pin "2") (pinfunction "2_2") (pintype "passive"))
      (node (ref "C124") (pin "2") (pinfunction "2_2") (pintype "passive"))
      (node (ref "C125") (pin "2") (pinfunction "2_2") (pintype "passive"))
      (node (ref "C126") (pin "2") (pinfunction "2_2") (pintype "passive"))
      (node (ref "C127") (pin "2") (pinfunction "2_2") (pintype "passive"))
      (node (ref "C128") (pin "2") (pinfunction "2_2") (pintype "passive"))
      (node (ref "C129") (pin "2") (pinfunction "2_2") (pintype "passive"))
      (node (ref "C131") (pin "2") (pinfunction "2_2") (pintype "passive"))
      (node (ref "C132") (pin "2") (pinfunction "2_2") (pintype "passive"))
      (node (ref "C133") (pin "2") (pinfunction "2_2") (pintype "passive"))
      (node (ref "C134") (pin "2") (pinfunction "2_2") (pintype "passive"))
      (node (ref "C135") (pin "2") (pinfunction "2_2") (pintype "passive"))
      (node (ref "C136") (pin "2") (pinfunction "2_2") (pintype "passive"))
      (node (ref "C140") (pin "2") (pinfunction "2_2") (pintype "passive"))
      (node (ref "C141") (pin "2") (pinfunction "2_2") (pintype "passive"))
      (node (ref "C143") (pin "2") (pinfunction "2_2") (pintype "passive"))
      (node (ref "C20") (pin "2") (pinfunction "2_2") (pintype "passive"))
      (node (ref "C21") (pin "2") (pinfunction "2_2") (pintype "passive"))
      (node (ref "C22") (pin "2") (pinfunction "2_2") (pintype "passive"))
      (node (ref "C23") (pin "2") (pinfunction "2_2") (pintype "passive"))
      (node (ref "C31") (pin "2") (pinfunction "2_2") (pintype "passive"))
      (node (ref "C32") (pin "2") (pinfunction "2_2") (pintype "passive"))
      (node (ref "R22") (pin "2") (pinfunction "2_2") (pintype "passive"))
      (node (ref "R229") (pin "1") (pinfunction "1_1") (pintype "passive"))
      (node (ref "R231") (pin "1") (pinfunction "1_1") (pintype "passive"))
      (node (ref "R234") (pin "1") (pinfunction "1_1") (pintype "passive"))
      (node (ref "R239") (pin "1") (pinfunction "1_1") (pintype "passive"))
      (node (ref "R24") (pin "1") (pinfunction "1_1") (pintype "passive"))
      (node (ref "R39") (pin "1") (pinfunction "1_1") (pintype "passive"))
      (node (ref "SW1") (pin "3") (pintype "passive"))
      (node (ref "SW2") (pin "3") (pintype "passive"))
      (node (ref "U4") (pin "F10") (pinfunction "VSS2_F10") (pintype "passive"))
      (node (ref "U4") (pin "F2") (pinfunction "VSS13_VSS18_F2") (pintype "passive"))
      (node (ref "U4") (pin "F6") (pinfunction "VSS3_F6") (pintype "passive"))
      (node (ref "U4") (pin "F7") (pinfunction "VSS11_F7") (pintype "passive"))
      (node (ref "U4") (pin "F8") (pinfunction "VSS10_F8") (pintype "passive"))
      (node (ref "U4") (pin "F9") (pinfunction "VSS15_F9") (pintype "passive"))
      (node (ref "U4") (pin "G10") (pinfunction "VSS9_G10") (pintype "passive"))
      (node (ref "U4") (pin "G12") (pinfunction "DSI_VSS_G12") (pintype "passive"))
      (node (ref "U4") (pin "G6") (pinfunction "VSS17_G6") (pintype "passive"))
      (node (ref "U4") (pin "H10") (pinfunction "VSS20_H10") (pintype "passive"))
      (node (ref "U4") (pin "H6") (pinfunction "VSS5_H6") (pintype "passive"))
      (node (ref "U4") (pin "J10") (pinfunction "VSS8_J10") (pintype "passive"))
      (node (ref "U4") (pin "J6") (pinfunction "VSS12_J6") (pintype "passive"))
      (node (ref "U4") (pin "K10") (pinfunction "VSS14_K10") (pintype "passive"))
      (node (ref "U4") (pin "K6") (pinfunction "VSS4_K6") (pintype "passive"))
      (node (ref "U4") (pin "K7") (pinfunction "VSS6_K7") (pintype "passive"))
      (node (ref "U4") (pin "K8") (pinfunction "VSS7_K8") (pintype "passive"))
      (node (ref "U4") (pin "K9") (pinfunction "VSS1_K9") (pintype "passive"))
      (node (ref "U4") (pin "L6") (pinfunction "VSS19_L6") (pintype "passive"))
      (node (ref "U4") (pin "M1") (pinfunction "VSSA_M1") (pintype "passive"))
      (node (ref "U4") (pin "N1") (pinfunction "VREF-_N1") (pintype "passive"))
    )
    (net (code "270") (name "Net-(BT1-+)") (class "Default")
      (node (ref "BT1") (pin "1") (pinfunction "+_1") (pintype "passive"))
      (node (ref "JP10") (pin "3") (pintype "passive"))
    )
    (net (code "271") (name "Net-(C20-Pad1)") (class "Default")
      (node (ref "C20") (pin "1") (pinfunction "1_1") (pintype "passive"))
      (node (ref "R20") (pin "2") (pinfunction "2_2") (pintype "passive"))
      (node (ref "X1") (pin "2") (pinfunction "2_2") (pintype "passive"))
    )
    (net (code "272") (name "Net-(C21-Pad1)") (class "Default")
      (node (ref "C21") (pin "1") (pinfunction "1_1") (pintype "passive"))
      (node (ref "R18") (pin "1") (pinfunction "1_1") (pintype "passive"))
      (node (ref "X2") (pin "1") (pinfunction "1_1") (pintype "passive"))
    )
    (net (code "273") (name "Net-(C22-Pad1)") (class "Default")
      (node (ref "C22") (pin "1") (pinfunction "1_1") (pintype "passive"))
      (node (ref "R19") (pin "1") (pinfunction "1_1") (pintype "passive"))
      (node (ref "X2") (pin "2") (pinfunction "2_2") (pintype "passive"))
    )
    (net (code "274") (name "Net-(D1-K)") (class "Default")
      (node (ref "D1") (pin "2") (pinfunction "K_2") (pintype "passive"))
      (node (ref "JP1") (pin "1") (pinfunction "COMMON_1") (pintype "passive"))
    )
    (net (code "275") (name "Net-(D2-K)") (class "Default")
      (node (ref "D2") (pin "2") (pinfunction "K_2") (pintype "passive"))
      (node (ref "JP4") (pin "1") (pinfunction "COMMON_1") (pintype "passive"))
    )
    (net (code "276") (name "Net-(R3-Pad2)") (class "Default")
      (node (ref "R3") (pin "2") (pinfunction "2_2") (pintype "passive"))
      (node (ref "SW1") (pin "2") (pintype "passive"))
    )
    (net (code "277") (name "Net-(R6-Pad1)") (class "Default")
      (node (ref "R6") (pin "1") (pinfunction "1_1") (pintype "passive"))
      (node (ref "SW2") (pin "2") (pintype "passive"))
    )
    (net (code "278") (name "Net-(R254-Pad1)") (class "Default")
      (node (ref "R254") (pin "1") (pinfunction "1_1") (pintype "passive"))
      (node (ref "SB27") (pin "2") (pinfunction "2_2") (pintype "passive"))
    )
    (net (code "279") (name "Net-(U4A-PB6)") (class "Default")
      (node (ref "R40") (pin "1") (pinfunction "1_1") (pintype "passive"))
      (node (ref "U4") (pin "B6") (pinfunction "PB6_B6") (pintype "passive"))
    )
    (net (code "280") (name "Net-(U4A-PDR_ON)") (class "Default")
      (node (ref "R21") (pin "1") (pinfunction "1_1") (pintype "passive"))
      (node (ref "R22") (pin "1") (pinfunction "1_1") (pintype "passive"))
      (node (ref "U4") (pin "E5") (pinfunction "PDR_ON_E5") (pintype "passive"))
    )
    (net (code "281") (name "Net-(U4B-PD0)") (class "Default")
      (node (ref "R262") (pin "1") (pinfunction "1_1") (pintype "passive"))
      (node (ref "U4") (pin "B12") (pinfunction "PD0_B12") (pintype "passive"))
    )
    (net (code "282") (name "Net-(U4B-PD1)") (class "Default")
      (node (ref "R273") (pin "1") (pinfunction "1_1") (pintype "passive"))
      (node (ref "U4") (pin "C12") (pinfunction "PD1_C12") (pintype "passive"))
    )
    (net (code "283") (name "Net-(U4B-PD8)") (class "Default")
      (node (ref "R56") (pin "1") (pinfunction "1_1") (pintype "passive"))
      (node (ref "U4") (pin "L15") (pinfunction "PD8_L15") (pintype "passive"))
    )
    (net (code "284") (name "Net-(U4B-PD9)") (class "Default")
      (node (ref "R65") (pin "1") (pinfunction "1_1") (pintype "passive"))
      (node (ref "U4") (pin "L14") (pinfunction "PD9_L14") (pintype "passive"))
    )
    (net (code "285") (name "Net-(U4B-PD10)") (class "Default")
      (node (ref "R66") (pin "1") (pinfunction "1_1") (pintype "passive"))
      (node (ref "U4") (pin "K15") (pinfunction "PD10_K15") (pintype "passive"))
    )
    (net (code "286") (name "Net-(U4B-PD11)") (class "Default")
      (node (ref "R260") (pin "2") (pinfunction "2_2") (pintype "passive"))
      (node (ref "U4") (pin "N10") (pinfunction "PD11_N10") (pintype "passive"))
    )
    (net (code "287") (name "Net-(U4B-PD12)") (class "Default")
      (node (ref "R271") (pin "1") (pinfunction "1_1") (pintype "passive"))
      (node (ref "U4") (pin "M10") (pinfunction "PD12_M10") (pintype "passive"))
    )
    (net (code "288") (name "Net-(U4B-PD13)") (class "Default")
      (node (ref "R258") (pin "1") (pinfunction "1_1") (pintype "passive"))
      (node (ref "U4") (pin "M11") (pinfunction "PD13_M11") (pintype "passive"))
    )
    (net (code "289") (name "Net-(U4B-PD14)") (class "Default")
      (node (ref "R268") (pin "1") (pinfunction "1_1") (pintype "passive"))
      (node (ref "U4") (pin "L12") (pinfunction "PD14_L12") (pintype "passive"))
    )
    (net (code "290") (name "Net-(U4B-PD15)") (class "Default")
      (node (ref "R256") (pin "1") (pinfunction "1_1") (pintype "passive"))
      (node (ref "U4") (pin "K13") (pinfunction "PD15_K13") (pintype "passive"))
    )
    (net (code "291") (name "Net-(U4B-PE2)") (class "Default")
      (node (ref "R238") (pin "2") (pinfunction "2_2") (pintype "passive"))
      (node (ref "R38") (pin "1") (pinfunction "1_1") (pintype "passive"))
      (node (ref "SB11") (pin "2") (pinfunction "2_2") (pintype "passive"))
      (node (ref "U4") (pin "A3") (pinfunction "PE2_A3") (pintype "passive"))
    )
    (net (code "292") (name "Net-(U4B-PE3)") (class "Default")
      (node (ref "R37") (pin "1") (pinfunction "1_1") (pintype "passive"))
      (node (ref "SB10") (pin "2") (pinfunction "2_2") (pintype "passive"))
      (node (ref "SB9") (pin "2") (pinfunction "2_2") (pintype "passive"))
      (node (ref "U4") (pin "A2") (pinfunction "PE3_A2") (pintype "passive"))
    )
    (net (code "293") (name "Net-(U4B-PE4)") (class "Default")
      (node (ref "R35") (pin "1") (pinfunction "1_1") (pintype "passive"))
      (node (ref "SB6") (pin "2") (pinfunction "2_2") (pintype "passive"))
      (node (ref "SB7") (pin "2") (pinfunction "2_2") (pintype "passive"))
      (node (ref "U4") (pin "A1") (pinfunction "PE4_A1") (pintype "passive"))
    )
    (net (code "294") (name "Net-(U4B-PE5)") (class "Default")
      (node (ref "R32") (pin "1") (pinfunction "1_1") (pintype "passive"))
      (node (ref "SB3") (pin "2") (pinfunction "2_2") (pintype "passive"))
      (node (ref "SB4") (pin "2") (pinfunction "2_2") (pintype "passive"))
      (node (ref "SB5") (pin "2") (pinfunction "2_2") (pintype "passive"))
      (node (ref "U4") (pin "B1") (pinfunction "PE5_B1") (pintype "passive"))
    )
    (net (code "295") (name "Net-(U4B-PE6)") (class "Default")
      (node (ref "R34") (pin "1") (pinfunction "1_1") (pintype "passive"))
      (node (ref "SB17") (pin "2") (pinfunction "2_2") (pintype "passive"))
      (node (ref "SB18") (pin "2") (pinfunction "2_2") (pintype "passive"))
      (node (ref "SB19") (pin "2") (pinfunction "2_2") (pintype "passive"))
      (node (ref "U4") (pin "B2") (pinfunction "PE6_B2") (pintype "passive"))
    )
    (net (code "296") (name "Net-(U4B-PE7)") (class "Default")
      (node (ref "R58") (pin "1") (pinfunction "1_1") (pintype "passive"))
      (node (ref "U4") (pin "R8") (pinfunction "PE7_R8") (pintype "passive"))
    )
    (net (code "297") (name "Net-(U4B-PE8)") (class "Default")
      (node (ref "R50") (pin "1") (pinfunction "1_1") (pintype "passive"))
      (node (ref "U4") (pin "N9") (pinfunction "PE8_N9") (pintype "passive"))
    )
    (net (code "298") (name "Net-(U4B-PE9)") (class "Default")
      (node (ref "R49") (pin "1") (pinfunction "1_1") (pintype "passive"))
      (node (ref "U4") (pin "P9") (pinfunction "PE9_P9") (pintype "passive"))
    )
    (net (code "299") (name "Net-(U4B-PE10)") (class "Default")
      (node (ref "R59") (pin "1") (pinfunction "1_1") (pintype "passive"))
      (node (ref "U4") (pin "R9") (pinfunction "PE10_R9") (pintype "passive"))
    )
    (net (code "300") (name "Net-(U4B-PE11)") (class "Default")
      (node (ref "R51") (pin "1") (pinfunction "1_1") (pintype "passive"))
      (node (ref "U4") (pin "P10") (pinfunction "PE11_P10") (pintype "passive"))
    )
    (net (code "301") (name "Net-(U4B-PE12)") (class "Default")
      (node (ref "R60") (pin "1") (pinfunction "1_1") (pintype "passive"))
      (node (ref "U4") (pin "R10") (pinfunction "PE12_R10") (pintype "passive"))
    )
    (net (code "302") (name "Net-(U4B-PE13)") (class "Default")
      (node (ref "R62") (pin "1") (pinfunction "1_1") (pintype "passive"))
      (node (ref "U4") (pin "R12") (pinfunction "PE13_R12") (pintype "passive"))
    )
    (net (code "303") (name "Net-(U4B-PE14)") (class "Default")
      (node (ref "R52") (pin "1") (pinfunction "1_1") (pintype "passive"))
      (node (ref "U4") (pin "P11") (pinfunction "PE14_P11") (pintype "passive"))
    )
    (net (code "304") (name "Net-(U4B-PE15)") (class "Default")
      (node (ref "R61") (pin "1") (pinfunction "1_1") (pintype "passive"))
      (node (ref "U4") (pin "R11") (pinfunction "PE15_R11") (pintype "passive"))
    )
    (net (code "305") (name "Net-(U4B-PF0)") (class "Default")
      (node (ref "R236") (pin "1") (pinfunction "1_1") (pintype "passive"))
      (node (ref "U4") (pin "D2") (pinfunction "PF0_D2") (pintype "passive"))
    )
    (net (code "306") (name "Net-(U4B-PF1)") (class "Default")
      (node (ref "R232") (pin "1") (pinfunction "1_1") (pintype "passive"))
      (node (ref "U4") (pin "E2") (pinfunction "PF1_E2") (pintype "passive"))
    )
    (net (code "307") (name "Net-(U4B-PF2)") (class "Default")
      (node (ref "R230") (pin "1") (pinfunction "1_1") (pintype "passive"))
      (node (ref "U4") (pin "G2") (pinfunction "PF2_G2") (pintype "passive"))
    )
    (net (code "308") (name "Net-(U4B-PF3)") (class "Default")
      (node (ref "R226") (pin "1") (pinfunction "1_1") (pintype "passive"))
      (node (ref "U4") (pin "H2") (pinfunction "PF3_H2") (pintype "passive"))
    )
    (net (code "309") (name "Net-(U4B-PF4)") (class "Default")
      (node (ref "R223") (pin "1") (pinfunction "1_1") (pintype "passive"))
      (node (ref "U4") (pin "J2") (pinfunction "PF4_J2") (pintype "passive"))
    )
    (net (code "310") (name "Net-(U4B-PF5)") (class "Default")
      (node (ref "R221") (pin "1") (pinfunction "1_1") (pintype "passive"))
      (node (ref "U4") (pin "K3") (pinfunction "PF5_K3") (pintype "passive"))
    )
    (net (code "311") (name "Net-(U4B-PF6)") (class "Default")
      (node (ref "R25") (pin "1") (pinfunction "1_1") (pintype "passive"))
      (node (ref "U4") (pin "K2") (pinfunction "PF6_K2") (pintype "passive"))
    )
    (net (code "312") (name "Net-(U4B-PF7)") (class "Default")
      (node (ref "R23") (pin "1") (pinfunction "1_1") (pintype "passive"))
      (node (ref "U4") (pin "K1") (pinfunction "PF7_K1") (pintype "passive"))
    )
    (net (code "313") (name "Net-(U4B-PF8)") (class "Default")
      (node (ref "R237") (pin "1") (pinfunction "1_1") (pintype "passive"))
      (node (ref "U4") (pin "L3") (pinfunction "PF8_L3") (pintype "passive"))
    )
    (net (code "314") (name "Net-(U4B-PF9)") (class "Default")
      (node (ref "R27") (pin "1") (pinfunction "1_1") (pintype "passive"))
      (node (ref "U4") (pin "L2") (pinfunction "PF9_L2") (pintype "passive"))
    )
    (net (code "315") (name "Net-(U4B-PF10)") (class "Default")
      (node (ref "R222") (pin "1") (pinfunction "1_1") (pintype "passive"))
      (node (ref "U4") (pin "L1") (pinfunction "PF10_L1") (pintype "passive"))
    )
    (net (code "316") (name "Net-(U4B-PF11)") (class "Default")
      (node (ref "R48") (pin "1") (pinfunction "1_1") (pintype "passive"))
      (node (ref "U4") (pin "P8") (pinfunction "PF11_P8") (pintype "passive"))
    )
    (net (code "317") (name "Net-(U4B-PF12)") (class "Default")
      (node (ref "R248") (pin "1") (pinfunction "1_1") (pintype "passive"))
      (node (ref "U4") (pin "M6") (pinfunction "PF12_M6") (pintype "passive"))
    )
    (net (code "318") (name "Net-(U4B-PF13)") (class "Default")
      (node (ref "R245") (pin "1") (pinfunction "1_1") (pintype "passive"))
      (node (ref "U4") (pin "N6") (pinfunction "PF13_N6") (pintype "passive"))
    )
    (net (code "319") (name "Net-(U4B-PF14)") (class "Default")
      (node (ref "R249") (pin "1") (pinfunction "1_1") (pintype "passive"))
      (node (ref "U4") (pin "P6") (pinfunction "PF14_P6") (pintype "passive"))
    )
    (net (code "320") (name "Net-(U4B-PF15)") (class "Default")
      (node (ref "R261") (pin "1") (pinfunction "1_1") (pintype "passive"))
      (node (ref "U4") (pin "M8") (pinfunction "PF15_M8") (pintype "passive"))
    )
    (net (code "321") (name "Net-(U4B-PG0)") (class "Default")
      (node (ref "R251") (pin "1") (pinfunction "1_1") (pintype "passive"))
      (node (ref "U4") (pin "N7") (pinfunction "PG0_N7") (pintype "passive"))
    )
    (net (code "322") (name "Net-(U4B-PG1)") (class "Default")
      (node (ref "R250") (pin "1") (pinfunction "1_1") (pintype "passive"))
      (node (ref "U4") (pin "M7") (pinfunction "PG1_M7") (pintype "passive"))
    )
    (net (code "323") (name "Net-(U4B-PG2)") (class "Default")
      (node (ref "R269") (pin "1") (pinfunction "1_1") (pintype "passive"))
      (node (ref "U4") (pin "M13") (pinfunction "PG2_M13") (pintype "passive"))
    )
    (net (code "324") (name "Net-(U4B-PG3)") (class "Default")
      (node (ref "R257") (pin "1") (pinfunction "1_1") (pintype "passive"))
      (node (ref "U4") (pin "M12") (pinfunction "PG3_M12") (pintype "passive"))
    )
    (net (code "325") (name "Net-(U4B-PG4)") (class "Default")
      (node (ref "R270") (pin "1") (pinfunction "1_1") (pintype "passive"))
      (node (ref "U4") (pin "N12") (pinfunction "PG4_N12") (pintype "passive"))
    )
    (net (code "326") (name "Net-(U4B-PG5)") (class "Default")
      (node (ref "R259") (pin "1") (pinfunction "1_1") (pintype "passive"))
      (node (ref "U4") (pin "N11") (pinfunction "PG5_N11") (pintype "passive"))
    )
    (net (code "327") (name "Net-(U4B-PG8)") (class "Default")
      (node (ref "R267") (pin "1") (pinfunction "1_1") (pintype "passive"))
      (node (ref "U4") (pin "H14") (pinfunction "PG8_H14") (pintype "passive"))
    )
    (net (code "328") (name "Net-(U4B-PG15)") (class "Default")
      (node (ref "R41") (pin "1") (pinfunction "1_1") (pintype "passive"))
      (node (ref "U4") (pin "B7") (pinfunction "PG15_B7") (pintype "passive"))
    )
    (net (code "329") (name "Net-(U4B-PH3)") (class "Default")
      (node (ref "R243") (pin "2") (pinfunction "2_2") (pintype "passive"))
      (node (ref "SB63") (pin "1") (pinfunction "1_1") (pintype "passive"))
      (node (ref "U4") (pin "J4") (pinfunction "PH3_J4") (pintype "passive"))
    )
    (net (code "330") (name "Net-(U4B-PH5)") (class "Default")
      (node (ref "R246") (pin "2") (pinfunction "2_2") (pintype "passive"))
      (node (ref "U4") (pin "J3") (pinfunction "PH5_J3") (pintype "passive"))
    )
    (net (code "331") (name "Net-(U4B-PH8)") (class "Default")
      (node (ref "R53") (pin "2") (pinfunction "2_2") (pintype "passive"))
      (node (ref "U4") (pin "P14") (pinfunction "PH8_P14") (pintype "passive"))
    )
    (net (code "332") (name "Net-(U4B-PH9)") (class "Default")
      (node (ref "R54") (pin "2") (pinfunction "2_2") (pintype "passive"))
      (node (ref "U4") (pin "N14") (pinfunction "PH9_N14") (pintype "passive"))
    )
    (net (code "333") (name "Net-(U4B-PH10)") (class "Default")
      (node (ref "R63") (pin "2") (pinfunction "2_2") (pintype "passive"))
      (node (ref "U4") (pin "P15") (pinfunction "PH10_P15") (pintype "passive"))
    )
    (net (code "334") (name "Net-(U4B-PH11)") (class "Default")
      (node (ref "R64") (pin "2") (pinfunction "2_2") (pintype "passive"))
      (node (ref "U4") (pin "N15") (pinfunction "PH11_N15") (pintype "passive"))
    )
    (net (code "335") (name "Net-(U4B-PH12)") (class "Default")
      (node (ref "R55") (pin "2") (pinfunction "2_2") (pintype "passive"))
      (node (ref "U4") (pin "M15") (pinfunction "PH12_M15") (pintype "passive"))
    )
    (net (code "336") (name "Net-(U4B-PH13)") (class "Default")
      (node (ref "R266") (pin "2") (pinfunction "2_2") (pintype "passive"))
      (node (ref "U4") (pin "E12") (pinfunction "PH13_E12") (pintype "passive"))
    )
    (net (code "337") (name "Net-(U4B-PH14)") (class "Default")
      (node (ref "R276") (pin "2") (pinfunction "2_2") (pintype "passive"))
      (node (ref "U4") (pin "E13") (pinfunction "PH14_E13") (pintype "passive"))
    )
    (net (code "338") (name "Net-(U4B-PH15)") (class "Default")
      (node (ref "R275") (pin "2") (pinfunction "2_2") (pintype "passive"))
      (node (ref "U4") (pin "D13") (pinfunction "PH15_D13") (pintype "passive"))
    )
    (net (code "339") (name "Net-(U4B-PI0)") (class "Default")
      (node (ref "R265") (pin "2") (pinfunction "2_2") (pintype "passive"))
      (node (ref "U4") (pin "E14") (pinfunction "PI0_E14") (pintype "passive"))
    )
    (net (code "340") (name "Net-(U4B-PI1)") (class "Default")
      (node (ref "R264") (pin "2") (pinfunction "2_2") (pintype "passive"))
      (node (ref "U4") (pin "D14") (pinfunction "PI1_D14") (pintype "passive"))
    )
    (net (code "341") (name "Net-(U4B-PI2)") (class "Default")
      (node (ref "R263") (pin "2") (pinfunction "2_2") (pintype "passive"))
      (node (ref "U4") (pin "C14") (pinfunction "PI2_C14") (pintype "passive"))
    )
    (net (code "342") (name "Net-(U4B-PI3)") (class "Default")
      (node (ref "R274") (pin "2") (pinfunction "2_2") (pintype "passive"))
      (node (ref "U4") (pin "C13") (pinfunction "PI3_C13") (pintype "passive"))
    )
    (net (code "343") (name "Net-(U4B-PI6)") (class "Default")
      (node (ref "R247") (pin "2") (pinfunction "2_2") (pintype "passive"))
      (node (ref "U4") (pin "D6") (pinfunction "PI6_D6") (pintype "passive"))
    )
    (net (code "344") (name "Net-(U4B-PI7)") (class "Default")
      (node (ref "R240") (pin "2") (pinfunction "2_2") (pintype "passive"))
      (node (ref "U4") (pin "D4") (pinfunction "PI7_D4") (pintype "passive"))
    )
    (net (code "345") (name "Net-(U4B-PI9)") (class "Default")
      (node (ref "R241") (pin "2") (pinfunction "2_2") (pintype "passive"))
      (node (ref "U4") (pin "E4") (pinfunction "PI9_E4") (pintype "passive"))
    )
    (net (code "346") (name "Net-(U4B-PI10)") (class "Default")
      (node (ref "R244") (pin "2") (pinfunction "2_2") (pintype "passive"))
      (node (ref "SB12") (pin "1") (pinfunction "1_1") (pintype "passive"))
      (node (ref "U4") (pin "D5") (pinfunction "PI10_D5") (pintype "passive"))
    )
    (net (code "347") (name "Net-(U4B-PI14)") (class "Default")
      (node (ref "R214") (pin "2") (pinfunction "2_2") (pintype "passive"))
      (node (ref "U4") (pin "H3") (pinfunction "PI14_H3") (pintype "passive"))
    )
    (net (code "348") (name "Net-(U4C-BYPASS-REG)") (class "Default")
      (node (ref "R239") (pin "2") (pinfunction "2_2") (pintype "passive"))
      (node (ref "U4") (pin "L5") (pinfunction "BYPASS-REG_L5") (pintype "passive"))
    )
    (net (code "349") (name "Net-(U4C-VBAT)") (class "Default")
      (node (ref "JP10") (pin "2") (pintype "passive"))
      (node (ref "U4") (pin "C1") (pinfunction "VBAT_C1") (pintype "passive"))
    )
    (net (code "350") (name "Net-(U4C-VCAP1)") (class "Default")
      (node (ref "C143") (pin "1") (pinfunction "1_1") (pintype "passive"))
      (node (ref "U4") (pin "L11") (pinfunction "VCAP1_L11") (pintype "passive"))
    )
    (net (code "351") (name "Net-(U4C-VCAP2)") (class "Default")
      (node (ref "C32") (pin "1") (pinfunction "1_1") (pintype "passive"))
      (node (ref "U4") (pin "E11") (pinfunction "VCAP2_E11") (pintype "passive"))
    )
    (net (code "352") (name "VBUS_FS1") (class "Default")
      (node (ref "R253") (pin "2") (pinfunction "2_2") (pintype "passive"))
    )
    (net (code "353") (name "VBUS_FS2") (class "Default")
      (node (ref "R255") (pin "1") (pinfunction "1_1") (pintype "passive"))
    )
    (net (code "354") (name "VDDA") (class "Default")
      (node (ref "C114") (pin "1") (pinfunction "1_1") (pintype "passive"))
      (node (ref "C116") (pin "2") (pinfunction "2_2") (pintype "passive"))
      (node (ref "L7") (pin "2") (pinfunction "2_2") (pintype "passive"))
      (node (ref "R33") (pin "1") (pinfunction "1_1") (pintype "passive"))
      (node (ref "TP9") (pin "1") (pinfunction "1_1") (pintype "passive"))
      (node (ref "U4") (pin "R1") (pinfunction "VDDA_R1") (pintype "passive"))
    )
    (net (code "355") (name "VDD_MCU") (class "Default")
      (node (ref "C109") (pin "1") (pinfunction "1_1") (pintype "passive"))
      (node (ref "C111") (pin "1") (pinfunction "1_1") (pintype "passive"))
      (node (ref "C112") (pin "1") (pinfunction "1_1") (pintype "passive"))
      (node (ref "C115") (pin "1") (pinfunction "1_1") (pintype "passive"))
      (node (ref "C117") (pin "1") (pinfunction "1_1") (pintype "passive"))
      (node (ref "C118") (pin "1") (pinfunction "1_1") (pintype "passive"))
      (node (ref "C119") (pin "1") (pinfunction "1_1") (pintype "passive"))
      (node (ref "C120") (pin "1") (pinfunction "1_1") (pintype "passive"))
      (node (ref "C121") (pin "1") (pinfunction "1_1") (pintype "passive"))
      (node (ref "C124") (pin "1") (pinfunction "1_1") (pintype "passive"))
      (node (ref "C125") (pin "1") (pinfunction "1_1") (pintype "passive"))
      (node (ref "C126") (pin "1") (pinfunction "1_1") (pintype "passive"))
      (node (ref "C127") (pin "1") (pinfunction "1_1") (pintype "passive"))
      (node (ref "C128") (pin "1") (pinfunction "1_1") (pintype "passive"))
      (node (ref "C129") (pin "1") (pinfunction "1_1") (pintype "passive"))
      (node (ref "C131") (pin "1") (pinfunction "1_1") (pintype "passive"))
      (node (ref "C132") (pin "1") (pinfunction "1_1") (pintype "passive"))
      (node (ref "C133") (pin "1") (pinfunction "1_1") (pintype "passive"))
      (node (ref "C134") (pin "1") (pinfunction "1_1") (pintype "passive"))
      (node (ref "C135") (pin "1") (pinfunction "1_1") (pintype "passive"))
      (node (ref "C136") (pin "1") (pinfunction "1_1") (pintype "passive"))
      (node (ref "L7") (pin "1") (pinfunction "1_1") (pintype "passive"))
      (node (ref "U4") (pin "E10") (pinfunction "VDD15_E10") (pintype "passive"))
      (node (ref "U4") (pin "E7") (pinfunction "VDD3_E7") (pintype "passive"))
      (node (ref "U4") (pin "E8") (pinfunction "VDD11_E8") (pintype "passive"))
      (node (ref "U4") (pin "E9") (pinfunction "VDD10_E9") (pintype "passive"))
      (node (ref "U4") (pin "F11") (pinfunction "VDD2_F11") (pintype "passive"))
      (node (ref "U4") (pin "F4") (pinfunction "VDD13_F4") (pintype "passive"))
      (node (ref "U4") (pin "F5") (pinfunction "VDD17_F5") (pintype "passive"))
      (node (ref "U4") (pin "G11") (pinfunction "VDD_USB33_G11") (pintype "passive"))
      (node (ref "U4") (pin "G5") (pinfunction "VDD18_G5") (pintype "passive"))
      (node (ref "U4") (pin "H11") (pinfunction "VDD_VREGDSI_H11") (pintype "passive"))
      (node (ref "U4") (pin "H5") (pinfunction "VDD5_H5") (pintype "passive"))
      (node (ref "U4") (pin "J11") (pinfunction "VDD8_J11") (pintype "passive"))
      (node (ref "U4") (pin "J5") (pinfunction "VDD12_J5") (pintype "passive"))
      (node (ref "U4") (pin "K11") (pinfunction "VDD14_K11") (pintype "passive"))
      (node (ref "U4") (pin "K5") (pinfunction "VDD4_K5") (pintype "passive"))
      (node (ref "U4") (pin "L10") (pinfunction "VDD1_L10") (pintype "passive"))
      (node (ref "U4") (pin "L7") (pinfunction "VDD19_L7") (pintype "passive"))
      (node (ref "U4") (pin "L8") (pinfunction "VDD6_L8") (pintype "passive"))
      (node (ref "U4") (pin "L9") (pinfunction "VDD7_L9") (pintype "passive"))
    )
    (net (code "356") (name "VREF+") (class "Default")
      (node (ref "C108") (pin "1") (pinfunction "1_1") (pintype "passive"))
      (node (ref "C113") (pin "2") (pinfunction "2_2") (pintype "passive"))
      (node (ref "R33") (pin "2") (pinfunction "2_2") (pintype "passive"))
      (node (ref "TP6") (pin "1") (pinfunction "1_1") (pintype "passive"))
      (node (ref "U4") (pin "P1") (pinfunction "VREF+_P1") (pintype "passive"))
    )
  )
)
